# Smart_Coaster_rev1.net
KiCad netlist of a schematic drawn in EasyEDA Pro
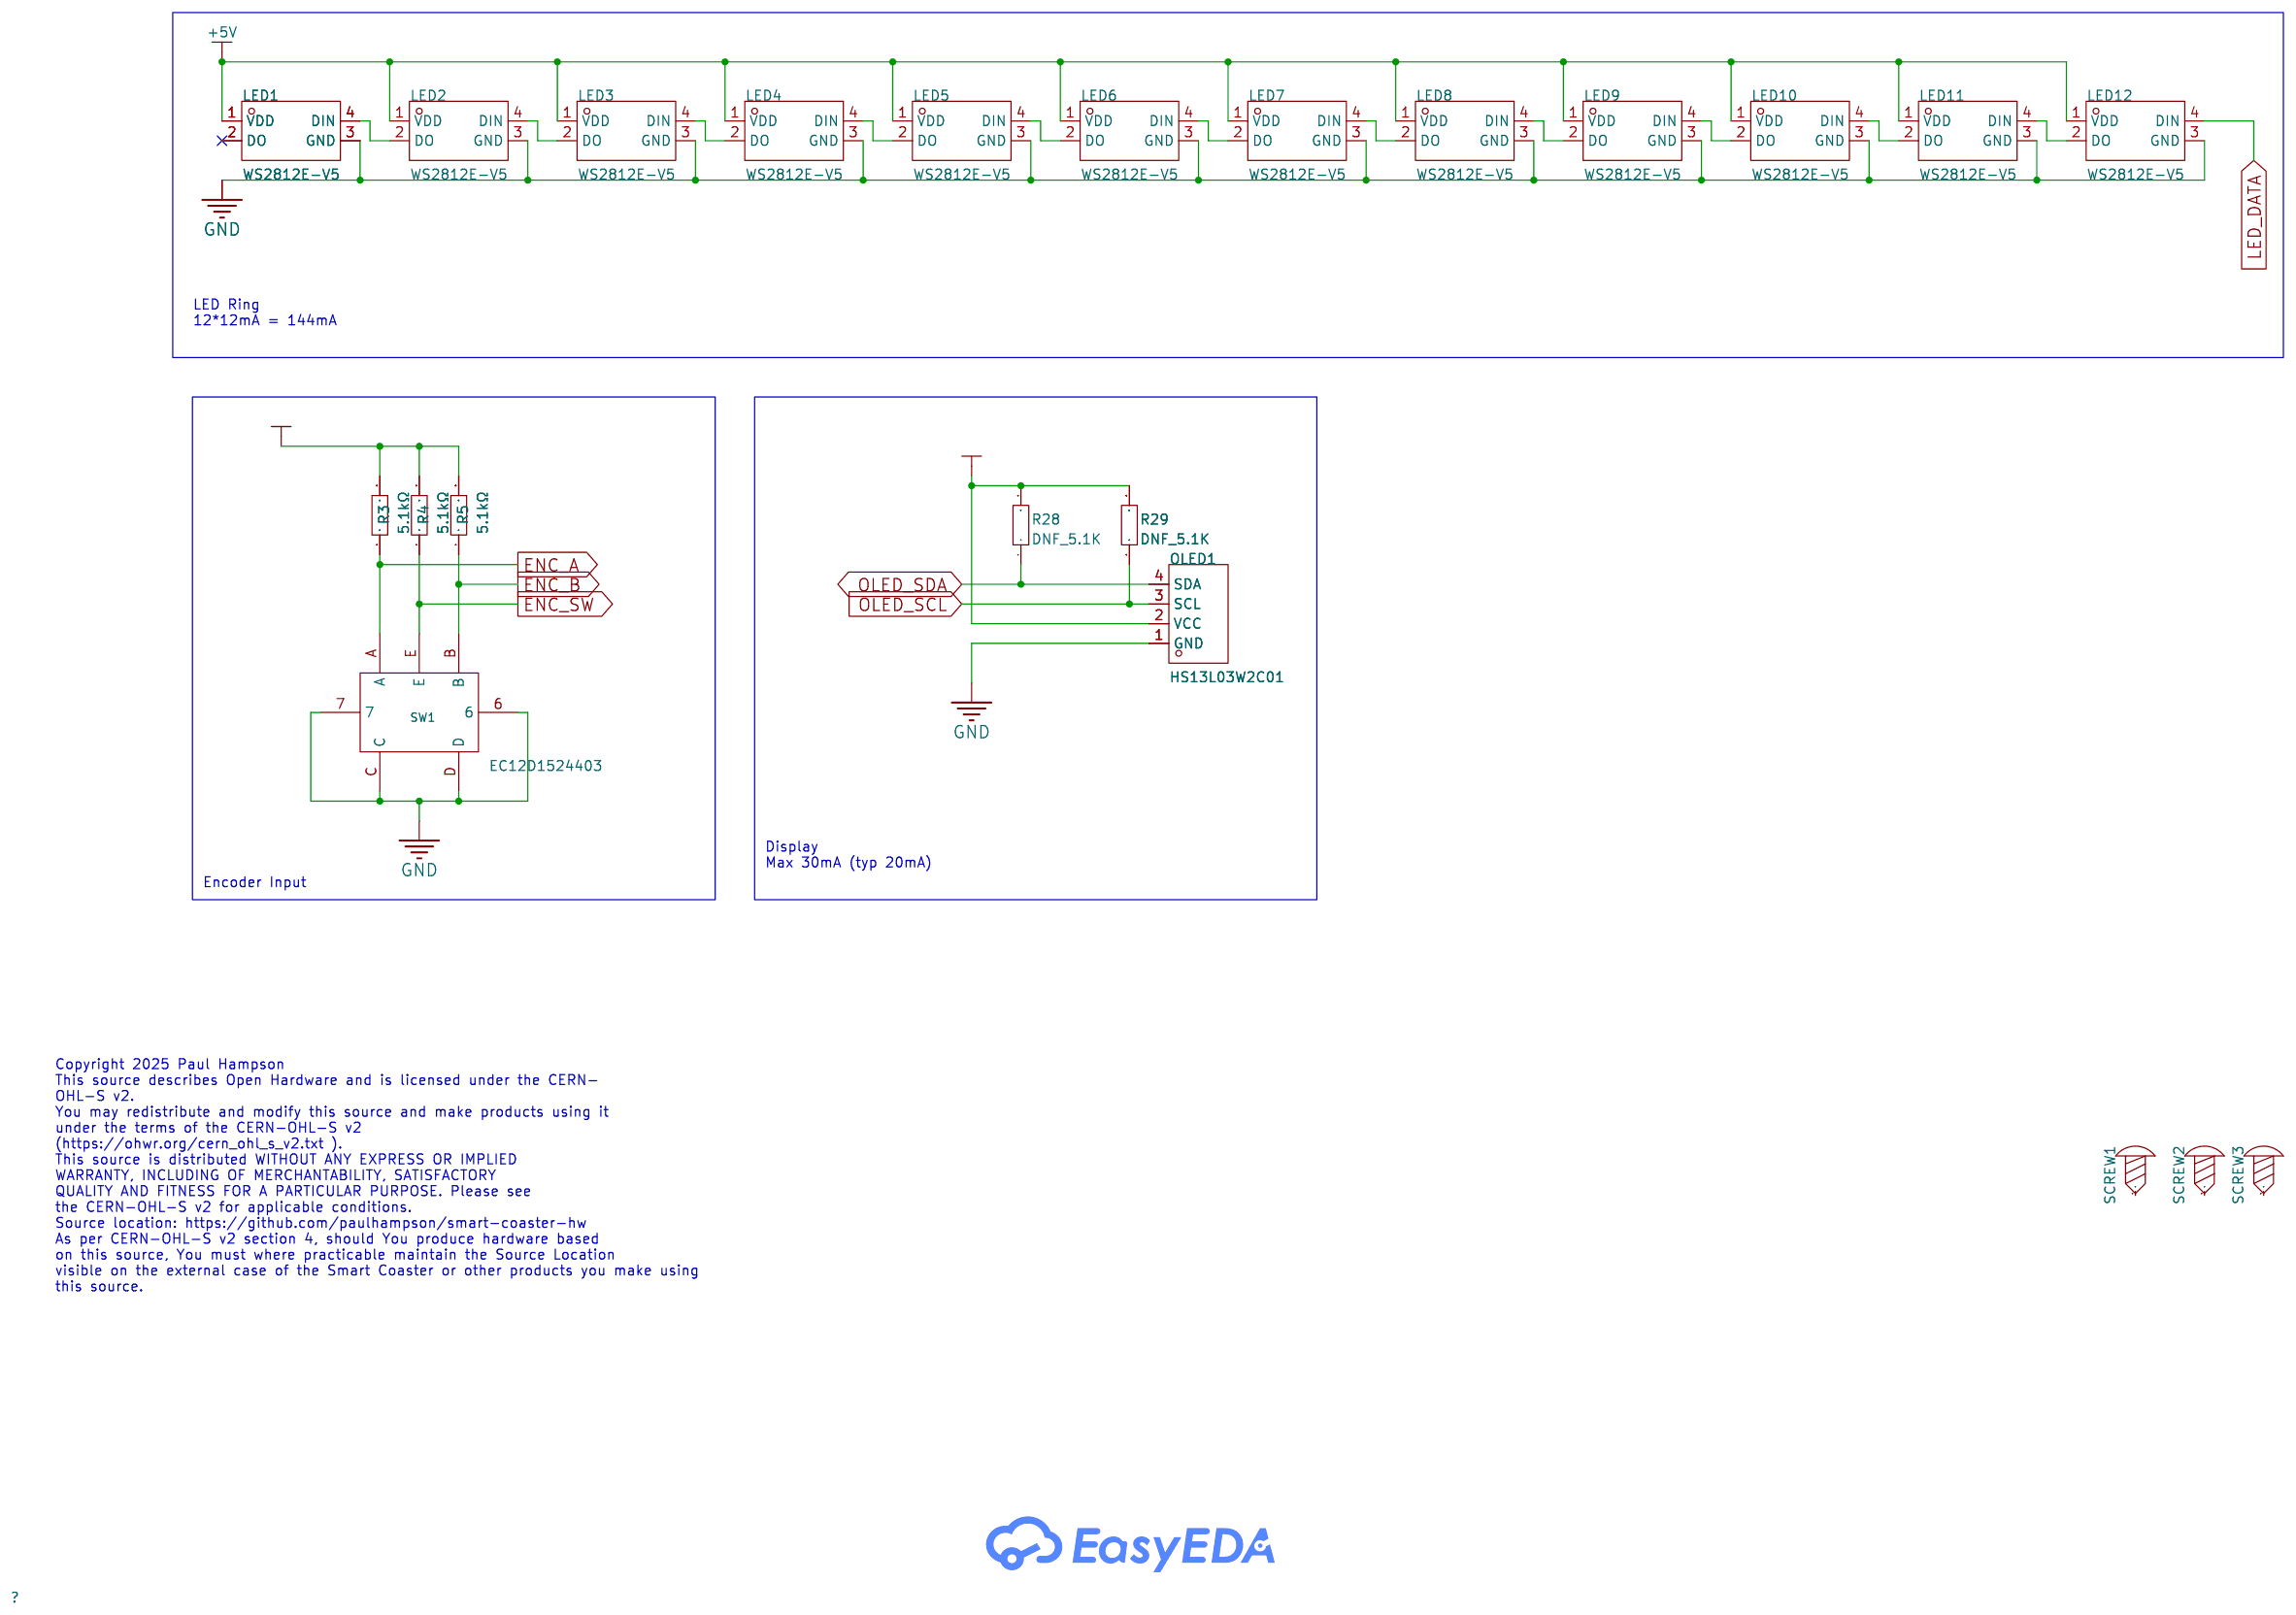
[diagram p0: HMI]
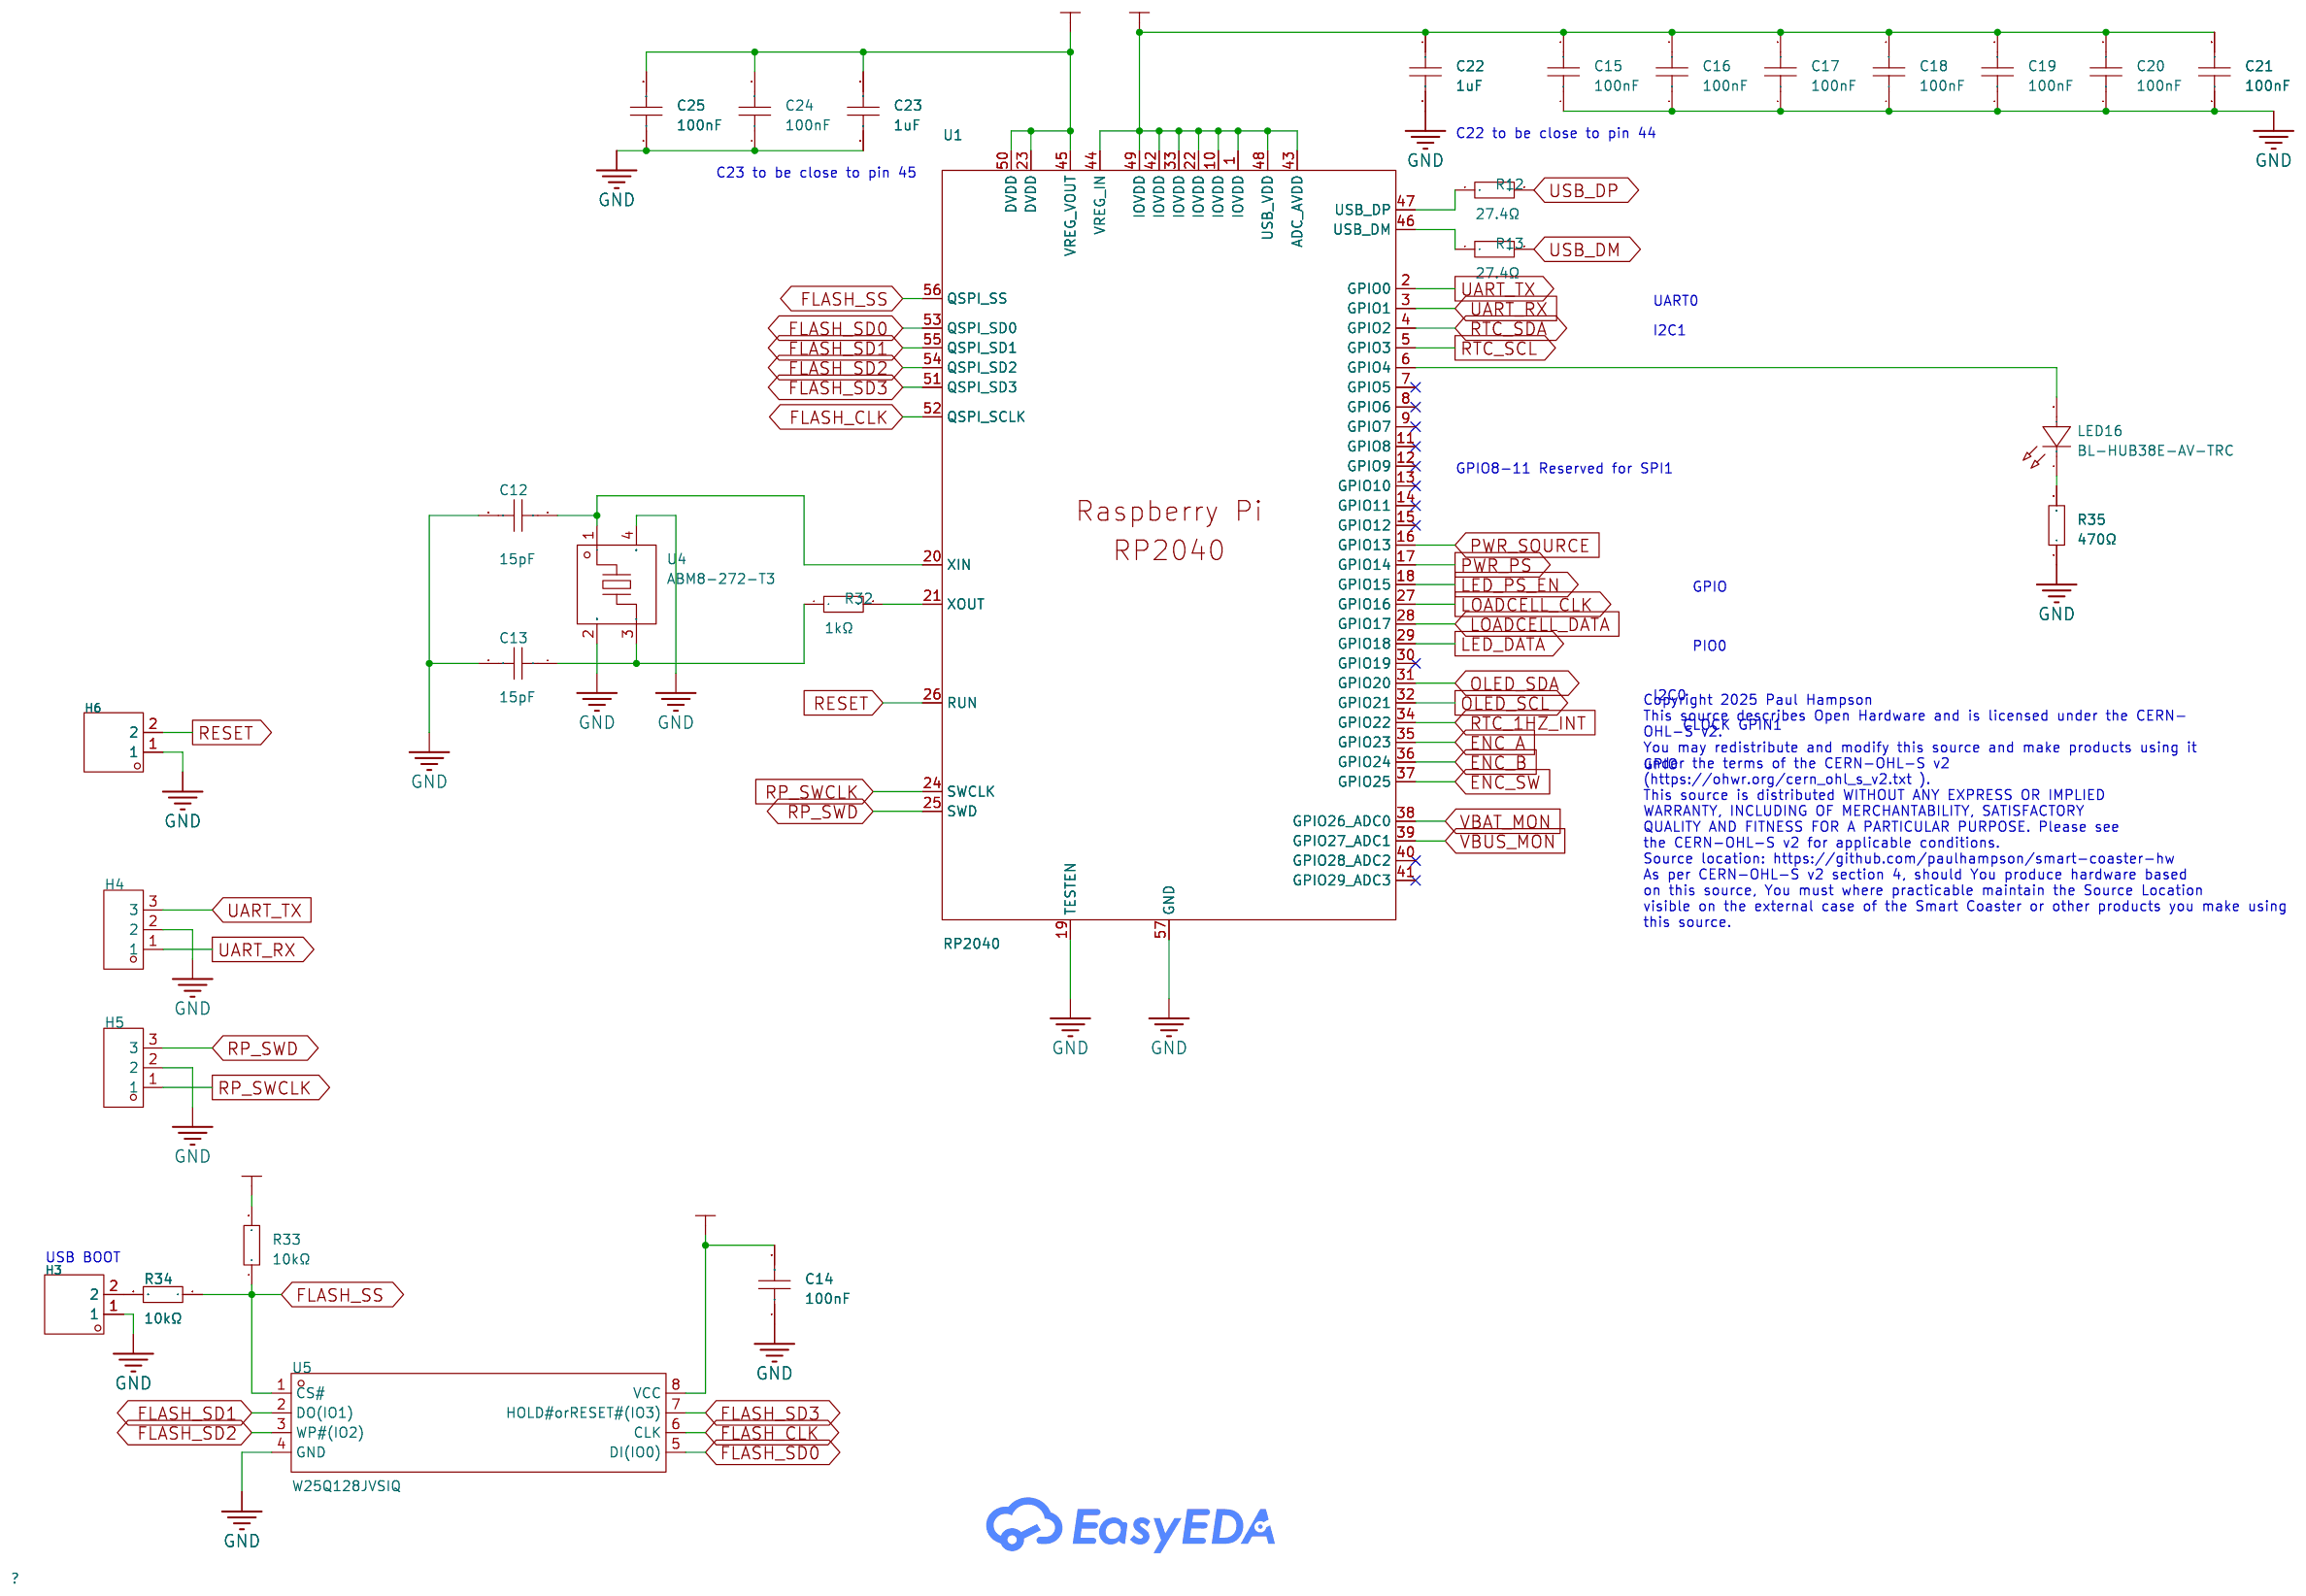
[diagram p1: Processor]
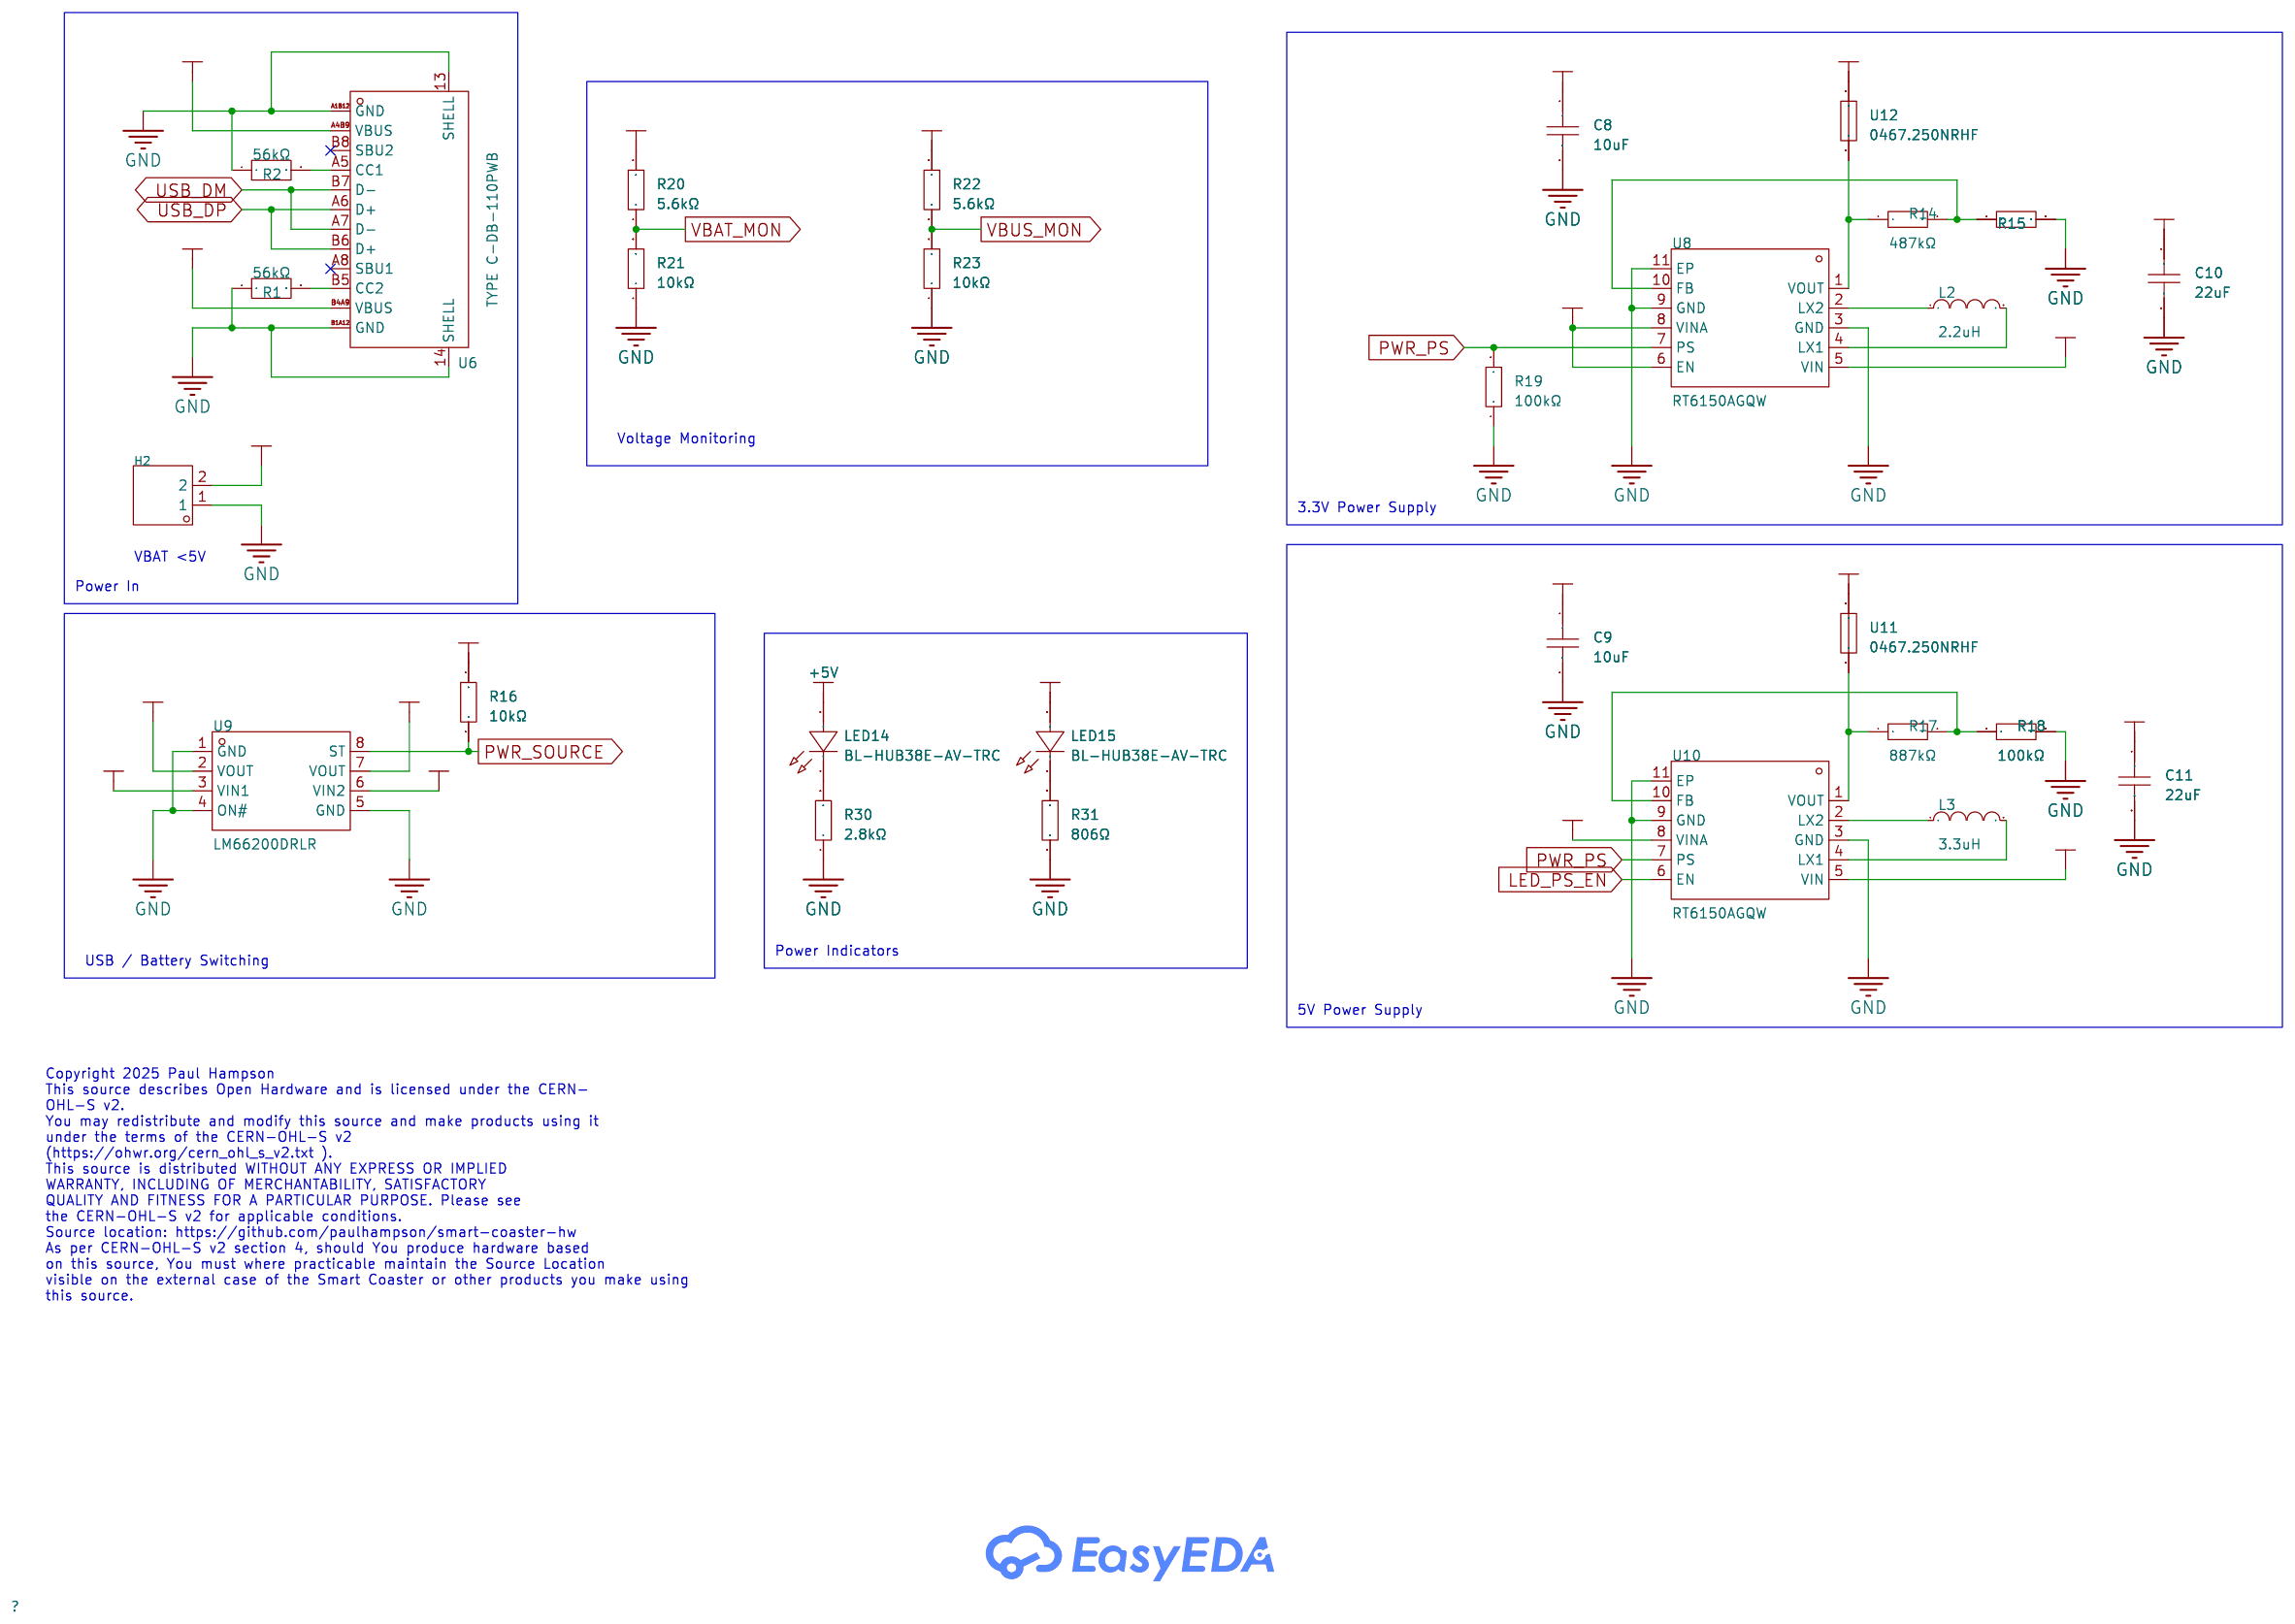
[diagram p2: Power]
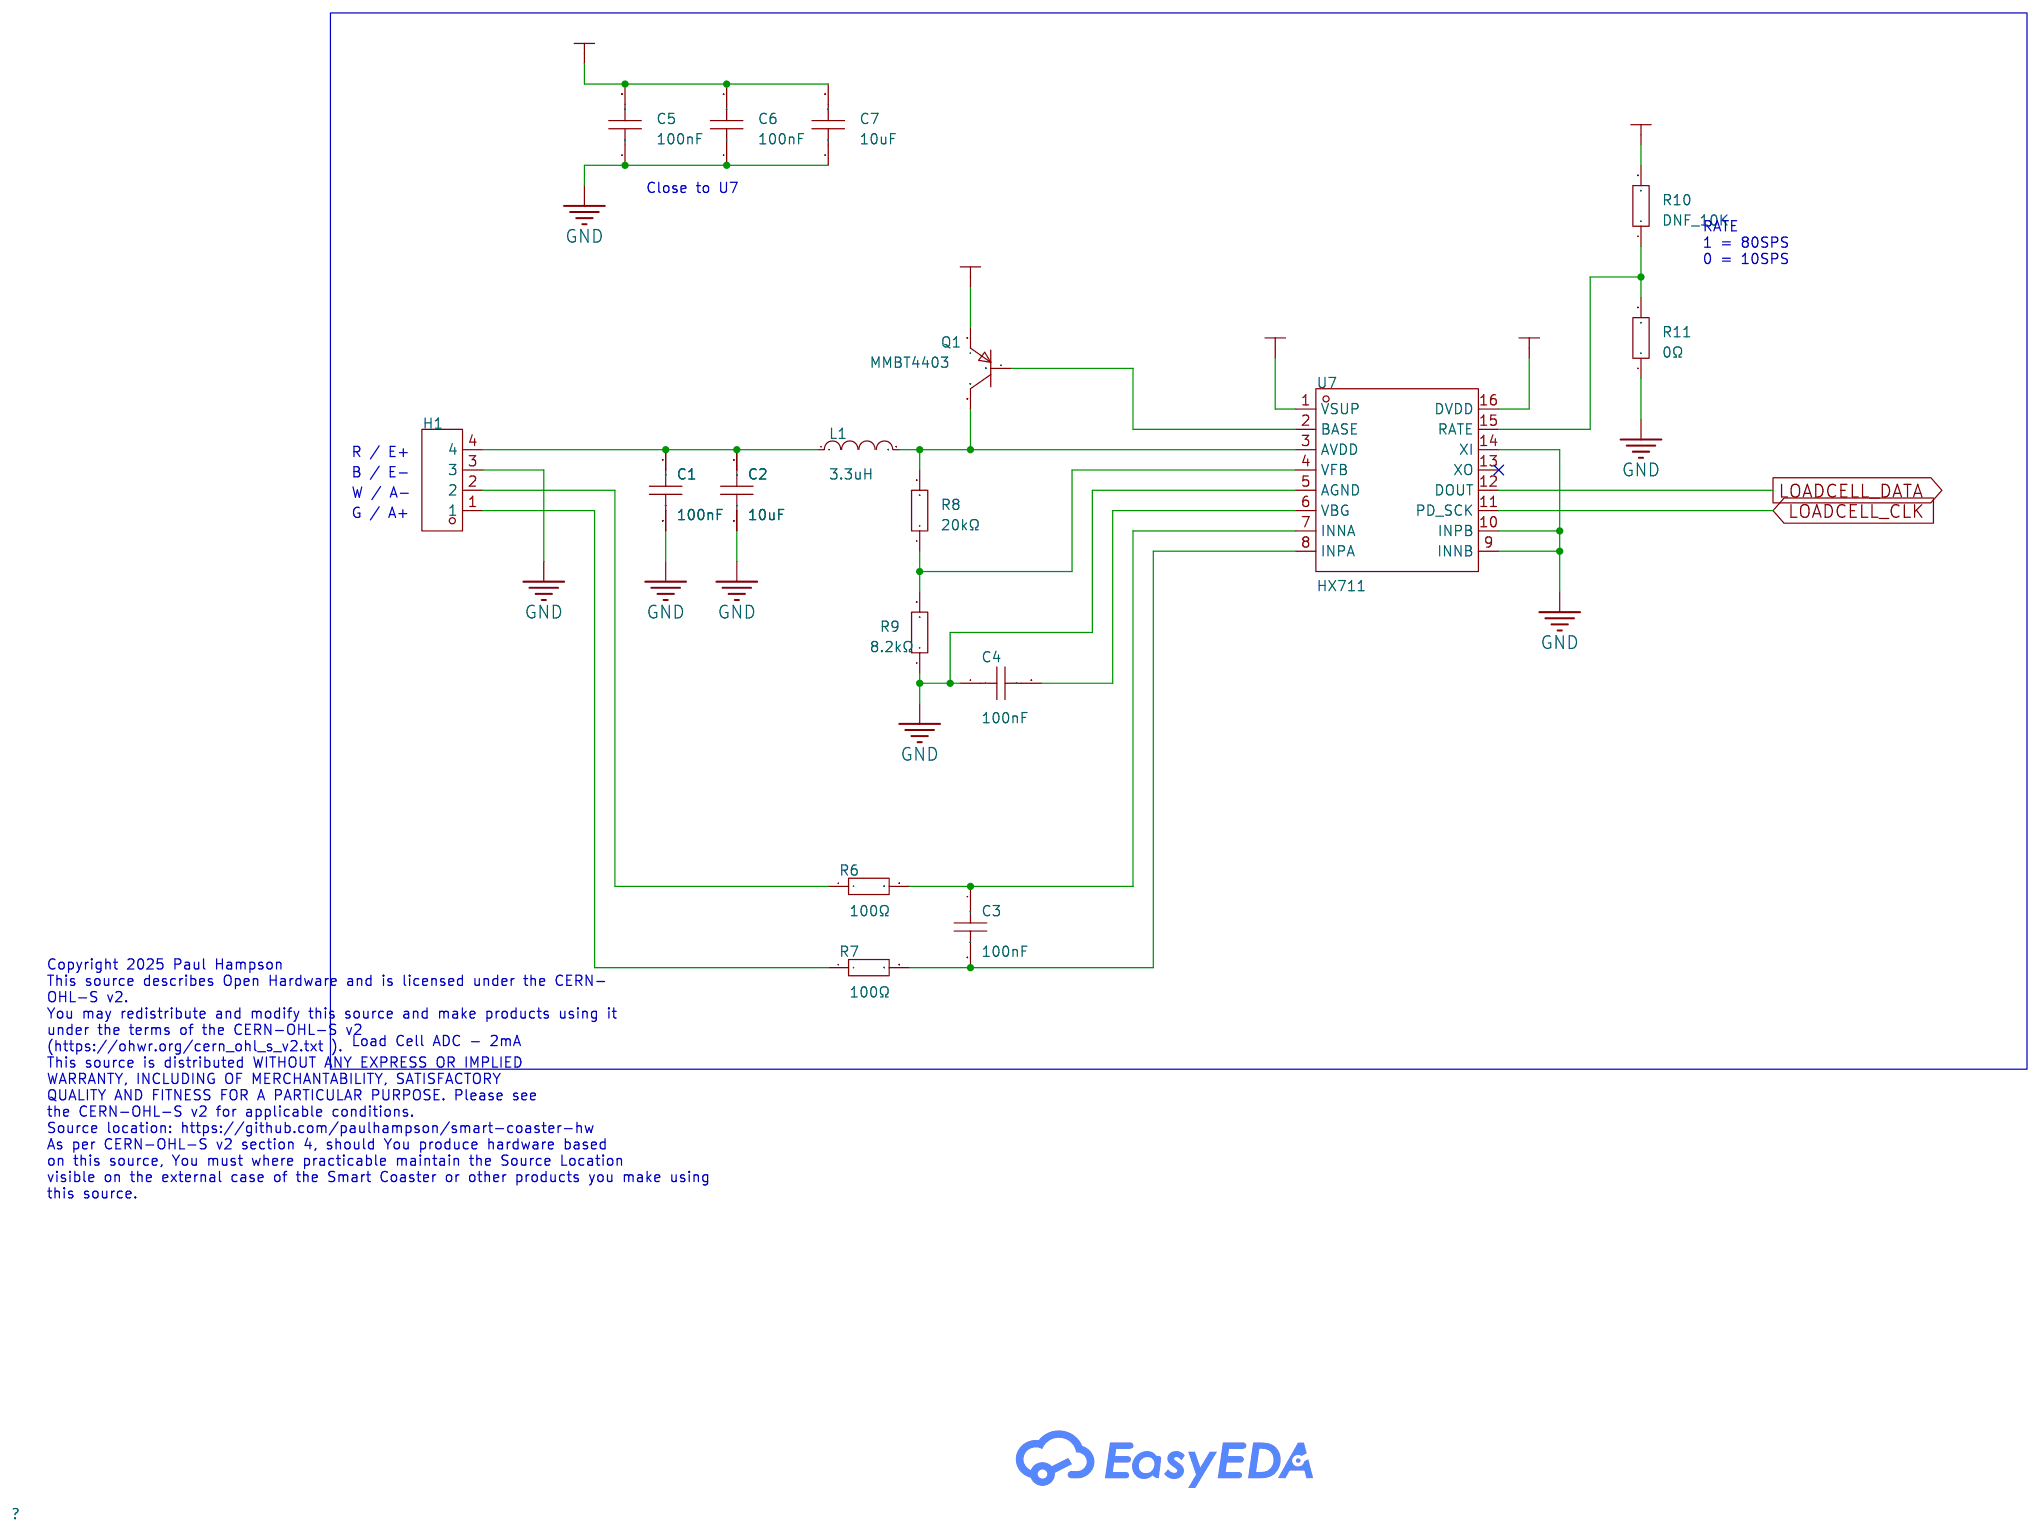
[diagram p3: Load Cell]
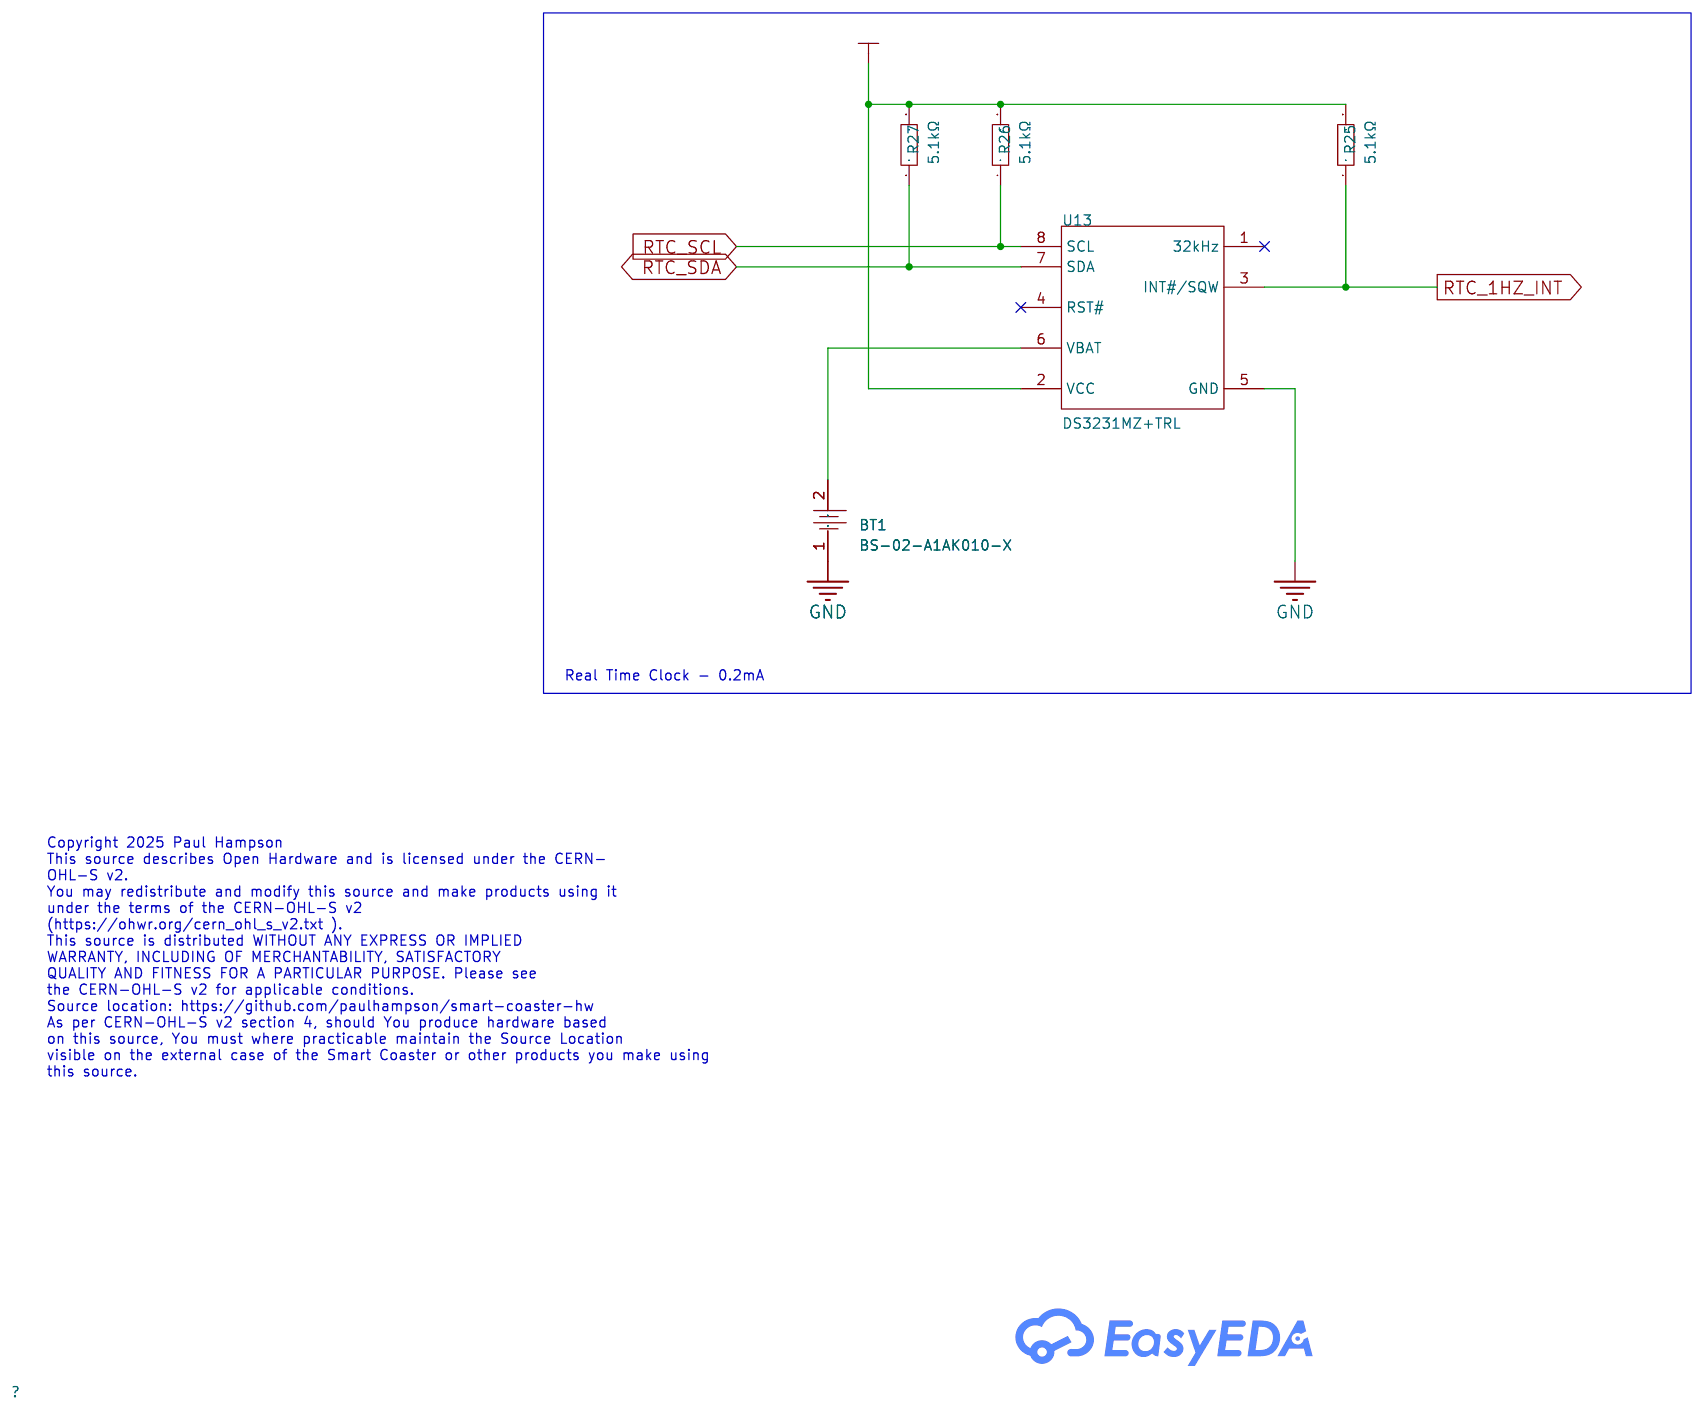
[diagram p4: RTC]

(export (version "E")
  (design (tool "Eeschema 10.0.6"))
  (components
    (comp (ref "LED1")
      (value "WS2812E-V5")
      (footprint "easyedapro:LED-SMD_4P-L5.0-W5.0-LS5.4-TL-1")
      (fields (field (name "Manufacturer") "worldsemi"))
      (libsource (lib "easyedapro") (part "WS2812E-V5"))
    )
    (comp (ref "LED2")
      (value "WS2812E-V5")
      (footprint "easyedapro:LED-SMD_4P-L5.0-W5.0-LS5.4-TL-1")
      (fields (field (name "Manufacturer") "worldsemi"))
      (libsource (lib "easyedapro") (part "WS2812E-V5"))
    )
    (comp (ref "LED3")
      (value "WS2812E-V5")
      (footprint "easyedapro:LED-SMD_4P-L5.0-W5.0-LS5.4-TL-1")
      (fields (field (name "Manufacturer") "worldsemi"))
      (libsource (lib "easyedapro") (part "WS2812E-V5"))
    )
    (comp (ref "LED4")
      (value "WS2812E-V5")
      (footprint "easyedapro:LED-SMD_4P-L5.0-W5.0-LS5.4-TL-1")
      (fields (field (name "Manufacturer") "worldsemi"))
      (libsource (lib "easyedapro") (part "WS2812E-V5"))
    )
    (comp (ref "LED5")
      (value "WS2812E-V5")
      (footprint "easyedapro:LED-SMD_4P-L5.0-W5.0-LS5.4-TL-1")
      (fields (field (name "Manufacturer") "worldsemi"))
      (libsource (lib "easyedapro") (part "WS2812E-V5"))
    )
    (comp (ref "LED6")
      (value "WS2812E-V5")
      (footprint "easyedapro:LED-SMD_4P-L5.0-W5.0-LS5.4-TL-1")
      (fields (field (name "Manufacturer") "worldsemi"))
      (libsource (lib "easyedapro") (part "WS2812E-V5"))
    )
    (comp (ref "LED7")
      (value "WS2812E-V5")
      (footprint "easyedapro:LED-SMD_4P-L5.0-W5.0-LS5.4-TL-1")
      (fields (field (name "Manufacturer") "worldsemi"))
      (libsource (lib "easyedapro") (part "WS2812E-V5"))
    )
    (comp (ref "LED8")
      (value "WS2812E-V5")
      (footprint "easyedapro:LED-SMD_4P-L5.0-W5.0-LS5.4-TL-1")
      (fields (field (name "Manufacturer") "worldsemi"))
      (libsource (lib "easyedapro") (part "WS2812E-V5"))
    )
    (comp (ref "LED9")
      (value "WS2812E-V5")
      (footprint "easyedapro:LED-SMD_4P-L5.0-W5.0-LS5.4-TL-1")
      (fields (field (name "Manufacturer") "worldsemi"))
      (libsource (lib "easyedapro") (part "WS2812E-V5"))
    )
    (comp (ref "LED10")
      (value "WS2812E-V5")
      (footprint "easyedapro:LED-SMD_4P-L5.0-W5.0-LS5.4-TL-1")
      (fields (field (name "Manufacturer") "worldsemi"))
      (libsource (lib "easyedapro") (part "WS2812E-V5"))
    )
    (comp (ref "LED11")
      (value "WS2812E-V5")
      (footprint "easyedapro:LED-SMD_4P-L5.0-W5.0-LS5.4-TL-1")
      (fields (field (name "Manufacturer") "worldsemi"))
      (libsource (lib "easyedapro") (part "WS2812E-V5"))
    )
    (comp (ref "LED12")
      (value "WS2812E-V5")
      (footprint "easyedapro:LED-SMD_4P-L5.0-W5.0-LS5.4-TL-1")
      (fields (field (name "Manufacturer") "worldsemi"))
      (libsource (lib "easyedapro") (part "WS2812E-V5"))
    )
    (comp (ref "OLED1")
      (value "HS13L03W2C01")
      (footprint "easyedapro:OLED-TH_L35.4-W33.5_HS13L03W2C01")
      (fields (field (name "Manufacturer") "HS(汉昇)"))
      (libsource (lib "easyedapro") (part "HS13L03W2C01"))
    )
    (comp (ref "R3")
      (value "5.1kΩ")
      (footprint "easyedapro:R0603")
      (fields
        (field (name "Manufacturer Part") "0603WAF5101T5E")
        (field (name "Manufacturer") "UNI-ROYAL(厚声)")
      )
      (libsource (lib "easyedapro") (part "0603WAF5101T5E"))
    )
    (comp (ref "R4")
      (value "5.1kΩ")
      (footprint "easyedapro:R0603")
      (fields
        (field (name "Manufacturer Part") "0603WAF5101T5E")
        (field (name "Manufacturer") "UNI-ROYAL(厚声)")
      )
      (libsource (lib "easyedapro") (part "0603WAF5101T5E"))
    )
    (comp (ref "R5")
      (value "5.1kΩ")
      (footprint "easyedapro:R0603")
      (fields
        (field (name "Manufacturer Part") "0603WAF5101T5E")
        (field (name "Manufacturer") "UNI-ROYAL(厚声)")
      )
      (libsource (lib "easyedapro") (part "0603WAF5101T5E"))
    )
    (comp (ref "R28")
      (value "DNF_5.1K")
      (footprint "easyedapro:R0402")
      (libsource (lib "easyedapro") (part "Res"))
    )
    (comp (ref "R29")
      (value "DNF_5.1K")
      (footprint "easyedapro:R0402")
      (libsource (lib "easyedapro") (part "Res"))
    )
    (comp (ref "SCREW1")
      (value "~")
      (footprint "easyedapro:Screw-Hole-M3")
      (libsource (lib "easyedapro") (part "Screw-Hole"))
    )
    (comp (ref "SCREW2")
      (value "~")
      (footprint "easyedapro:Screw-Hole-M3")
      (libsource (lib "easyedapro") (part "Screw-Hole"))
    )
    (comp (ref "SCREW3")
      (value "~")
      (footprint "easyedapro:Screw-Hole-M3")
      (libsource (lib "easyedapro") (part "Screw-Hole"))
    )
    (comp (ref "SW1")
      (value "EC12D1524403")
      (footprint "easyedapro:SW-TH_EC12D1524403")
      (fields (field (name "Manufacturer") "ALPSALPINE(阿尔卑斯阿尔派)"))
      (libsource (lib "easyedapro") (part "EC12D1524403"))
    )
    (comp (ref "C12")
      (value "15pF")
      (footprint "easyedapro:C0603")
      (fields
        (field (name "Manufacturer Part") "CC0402JRNPO9BN150")
        (field (name "Manufacturer") "YAGEO(国巨)")
      )
      (libsource (lib "easyedapro") (part "CAP"))
    )
    (comp (ref "C13")
      (value "15pF")
      (footprint "easyedapro:C0603")
      (fields
        (field (name "Manufacturer Part") "CC0402JRNPO9BN150")
        (field (name "Manufacturer") "YAGEO(国巨)")
      )
      (libsource (lib "easyedapro") (part "CAP"))
    )
    (comp (ref "C14")
      (value "100nF")
      (footprint "easyedapro:C0402")
      (fields
        (field (name "Manufacturer Part") "CL05B104KO5NNNC")
        (field (name "Manufacturer") "SAMSUNG(三星)")
      )
      (libsource (lib "easyedapro") (part "CL05B104KO5NNNC"))
    )
    (comp (ref "C15")
      (value "100nF")
      (footprint "easyedapro:C0402")
      (fields
        (field (name "Manufacturer Part") "CL05B104KO5NNNC")
        (field (name "Manufacturer") "SAMSUNG(三星)")
      )
      (libsource (lib "easyedapro") (part "CL05B104KO5NNNC"))
    )
    (comp (ref "C16")
      (value "100nF")
      (footprint "easyedapro:C0402")
      (fields
        (field (name "Manufacturer Part") "CL05B104KO5NNNC")
        (field (name "Manufacturer") "SAMSUNG(三星)")
      )
      (libsource (lib "easyedapro") (part "CL05B104KO5NNNC"))
    )
    (comp (ref "C17")
      (value "100nF")
      (footprint "easyedapro:C0402")
      (fields
        (field (name "Manufacturer Part") "CL05B104KO5NNNC")
        (field (name "Manufacturer") "SAMSUNG(三星)")
      )
      (libsource (lib "easyedapro") (part "CL05B104KO5NNNC"))
    )
    (comp (ref "C18")
      (value "100nF")
      (footprint "easyedapro:C0402")
      (fields
        (field (name "Manufacturer Part") "CL05B104KO5NNNC")
        (field (name "Manufacturer") "SAMSUNG(三星)")
      )
      (libsource (lib "easyedapro") (part "CL05B104KO5NNNC"))
    )
    (comp (ref "C19")
      (value "100nF")
      (footprint "easyedapro:C0402")
      (fields
        (field (name "Manufacturer Part") "CL05B104KO5NNNC")
        (field (name "Manufacturer") "SAMSUNG(三星)")
      )
      (libsource (lib "easyedapro") (part "CL05B104KO5NNNC"))
    )
    (comp (ref "C20")
      (value "100nF")
      (footprint "easyedapro:C0402")
      (fields
        (field (name "Manufacturer Part") "CL05B104KO5NNNC")
        (field (name "Manufacturer") "SAMSUNG(三星)")
      )
      (libsource (lib "easyedapro") (part "CL05B104KO5NNNC"))
    )
    (comp (ref "C21")
      (value "100nF")
      (footprint "easyedapro:C0402")
      (fields
        (field (name "Manufacturer Part") "CL05B104KO5NNNC")
        (field (name "Manufacturer") "SAMSUNG(三星)")
      )
      (libsource (lib "easyedapro") (part "CL05B104KO5NNNC"))
    )
    (comp (ref "C22")
      (value "1uF")
      (footprint "easyedapro:C0603")
      (fields
        (field (name "Manufacturer Part") "CL05A105KP5NNNC")
        (field (name "Manufacturer") "SAMSUNG(三星)")
      )
      (libsource (lib "easyedapro") (part "CAP"))
    )
    (comp (ref "C23")
      (value "1uF")
      (footprint "easyedapro:C0603")
      (fields
        (field (name "Manufacturer Part") "CL05A105KP5NNNC")
        (field (name "Manufacturer") "SAMSUNG(三星)")
      )
      (libsource (lib "easyedapro") (part "CAP"))
    )
    (comp (ref "C24")
      (value "100nF")
      (footprint "easyedapro:C0402")
      (fields
        (field (name "Manufacturer Part") "CL05B104KO5NNNC")
        (field (name "Manufacturer") "SAMSUNG(三星)")
      )
      (libsource (lib "easyedapro") (part "CL05B104KO5NNNC"))
    )
    (comp (ref "C25")
      (value "100nF")
      (footprint "easyedapro:C0402")
      (fields
        (field (name "Manufacturer Part") "CL05B104KO5NNNC")
        (field (name "Manufacturer") "SAMSUNG(三星)")
      )
      (libsource (lib "easyedapro") (part "CL05B104KO5NNNC"))
    )
    (comp (ref "H3")
      (value "~")
      (footprint "easyedapro:HDR-TH_2P-P2.54-V-M-1")
      (libsource (lib "easyedapro") (part "210S-1*2P L=11.6MMGold-plated black"))
    )
    (comp (ref "H4")
      (value "~")
      (footprint "easyedapro:HDR-TH_3P-P2.54-V-M")
      (libsource (lib "easyedapro") (part "PZ254V-11-03P_C2937625"))
    )
    (comp (ref "H5")
      (value "~")
      (footprint "easyedapro:HDR-TH_3P-P2.54-V-M")
      (libsource (lib "easyedapro") (part "PZ254V-11-03P_C2937625"))
    )
    (comp (ref "H6")
      (value "~")
      (footprint "easyedapro:HDR-TH_2P-P2.54-V-M-1")
      (libsource (lib "easyedapro") (part "210S-1*2P L=11.6MMGold-plated black"))
    )
    (comp (ref "LED16")
      (value "BL-HUB38E-AV-TRC")
      (footprint "easyedapro:LED-SMD_L1.7-W1.1-RD_RED-SIDE")
      (description "Emitted Color:Red Forward Current:-")
      (fields (field (name "Manufacturer") "BrtLed(佰鸿)"))
      (libsource (lib "easyedapro") (part "BL-HUB38E-AV-TRC"))
    )
    (comp (ref "R12")
      (value "27.4Ω")
      (footprint "easyedapro:R0402")
      (fields
        (field (name "Manufacturer Part") "0402WGF274JTCE")
        (field (name "Manufacturer") "UNI-ROYAL(厚声)")
      )
      (libsource (lib "easyedapro") (part "Res"))
    )
    (comp (ref "R13")
      (value "27.4Ω")
      (footprint "easyedapro:R0402")
      (fields
        (field (name "Manufacturer Part") "0402WGF274JTCE")
        (field (name "Manufacturer") "UNI-ROYAL(厚声)")
      )
      (libsource (lib "easyedapro") (part "Res"))
    )
    (comp (ref "R32")
      (value "1kΩ")
      (footprint "easyedapro:R0402")
      (fields
        (field (name "Manufacturer Part") "0402WGF1001TCE")
        (field (name "Manufacturer") "UNI-ROYAL(厚声)")
      )
      (libsource (lib "easyedapro") (part "Res"))
    )
    (comp (ref "R33")
      (value "10kΩ")
      (footprint "easyedapro:R0402")
      (fields
        (field (name "Manufacturer Part") "0402WGJ0103TCE")
        (field (name "Manufacturer") "UNI-ROYAL(厚声)")
      )
      (libsource (lib "easyedapro") (part "Res"))
    )
    (comp (ref "R34")
      (value "10kΩ")
      (footprint "easyedapro:R0402")
      (fields
        (field (name "Manufacturer Part") "0402WGJ0103TCE")
        (field (name "Manufacturer") "UNI-ROYAL(厚声)")
      )
      (libsource (lib "easyedapro") (part "Res"))
    )
    (comp (ref "R35")
      (value "470Ω")
      (footprint "easyedapro:R0402")
      (fields
        (field (name "Manufacturer Part") "0402WGF4700TCE")
        (field (name "Manufacturer") "UNI-ROYAL(厚声)")
      )
      (libsource (lib "easyedapro") (part "Res"))
    )
    (comp (ref "U1")
      (value "RP2040")
      (footprint "easyedapro:LQFN-56_L7.0-W7.0-P0.4-EP")
      (fields (field (name "Manufacturer") "Raspberry Pi(树莓派)"))
      (libsource (lib "easyedapro") (part "RP2040"))
    )
    (comp (ref "U4")
      (value "ABM8-272-T3")
      (footprint "easyedapro:CRYSTAL-SMD_4P-L3.2-W2.5-BL")
      (fields (field (name "Manufacturer") "ABRACON"))
      (libsource (lib "easyedapro") (part "ABM8-272-T3_C20625731"))
    )
    (comp (ref "U5")
      (value "W25Q128JVSIQ")
      (footprint "easyedapro:SOIC-8_L5.3-W5.3-P1.27-LS8.0-BL")
      (fields (field (name "Manufacturer") "WINBOND(华邦)"))
      (libsource (lib "easyedapro") (part "W25Q128JVSIQ"))
    )
    (comp (ref "C8")
      (value "10uF")
      (footprint "easyedapro:C0603")
      (fields
        (field (name "Manufacturer Part") "CL10A106MQ8NNNC")
        (field (name "Manufacturer") "SAMSUNG(三星)")
      )
      (libsource (lib "easyedapro") (part "CAP"))
    )
    (comp (ref "C9")
      (value "10uF")
      (footprint "easyedapro:C0603")
      (fields
        (field (name "Manufacturer Part") "CL10A106MQ8NNNC")
        (field (name "Manufacturer") "SAMSUNG(三星)")
      )
      (libsource (lib "easyedapro") (part "CAP"))
    )
    (comp (ref "C10")
      (value "22uF")
      (footprint "easyedapro:C0603")
      (fields
        (field (name "Manufacturer Part") "CL21A226MAYNNNE")
        (field (name "Manufacturer") "SAMSUNG(三星)")
      )
      (libsource (lib "easyedapro") (part "CAP"))
    )
    (comp (ref "C11")
      (value "22uF")
      (footprint "easyedapro:C0603")
      (fields
        (field (name "Manufacturer Part") "CL21A226MAYNNNE")
        (field (name "Manufacturer") "SAMSUNG(三星)")
      )
      (libsource (lib "easyedapro") (part "CAP"))
    )
    (comp (ref "H2")
      (value "~")
      (footprint "easyedapro:HDR-TH_2P-P2.54-V-M-1")
      (libsource (lib "easyedapro") (part "210S-1*2P L=11.6MMGold-plated black"))
    )
    (comp (ref "L2")
      (value "2.2uH")
      (footprint "easyedapro:L0603")
      (fields (field (name "Manufacturer Part") "AHW2012F-2R2KTF") (field (name "Manufacturer") "APV(爱普微)"))
      (libsource (lib "easyedapro") (part "电感"))
    )
    (comp (ref "L3")
      (value "3.3uH")
      (footprint "easyedapro:L0603")
      (fields (field (name "Manufacturer Part") "AHW2012F-3R3KTF") (field (name "Manufacturer") "APV(爱普微)"))
      (libsource (lib "easyedapro") (part "电感"))
    )
    (comp (ref "LED14")
      (value "BL-HUB38E-AV-TRC")
      (footprint "easyedapro:LED-SMD_L1.7-W1.1-RD_RED-SIDE")
      (description "Emitted Color:Red Forward Current:-")
      (fields (field (name "Manufacturer") "BrtLed(佰鸿)"))
      (libsource (lib "easyedapro") (part "BL-HUB38E-AV-TRC"))
    )
    (comp (ref "LED15")
      (value "BL-HUB38E-AV-TRC")
      (footprint "easyedapro:LED-SMD_L1.7-W1.1-RD_RED-SIDE")
      (description "Emitted Color:Red Forward Current:-")
      (fields (field (name "Manufacturer") "BrtLed(佰鸿)"))
      (libsource (lib "easyedapro") (part "BL-HUB38E-AV-TRC"))
    )
    (comp (ref "R1")
      (value "56kΩ")
      (footprint "easyedapro:R0603")
      (fields (field (name "Manufacturer Part") "SCR0603J56K") (field (name "Manufacturer") "VO(翔胜)"))
      (libsource (lib "easyedapro") (part "SCR0603J56K"))
    )
    (comp (ref "R2")
      (value "56kΩ")
      (footprint "easyedapro:R0603")
      (fields (field (name "Manufacturer Part") "SCR0603J56K") (field (name "Manufacturer") "VO(翔胜)"))
      (libsource (lib "easyedapro") (part "SCR0603J56K"))
    )
    (comp (ref "R14")
      (value "487kΩ")
      (footprint "easyedapro:R0402")
      (fields
        (field (name "Manufacturer Part") "0603WAF4873T5E")
        (field (name "Manufacturer") "UNI-ROYAL(厚声)")
      )
      (libsource (lib "easyedapro") (part "Res"))
    )
    (comp (ref "R15")
      (value "86.6kΩ")
      (footprint "easyedapro:R0603")
      (fields
        (field (name "Manufacturer Part") "0603WAF8662T5E")
        (field (name "Manufacturer") "UNI-ROYAL(厚声)")
      )
      (libsource (lib "easyedapro") (part "0603WAF8662T5E"))
    )
    (comp (ref "R16")
      (value "10kΩ")
      (footprint "easyedapro:R0402")
      (fields
        (field (name "Manufacturer Part") "0603WAF1002T5E")
        (field (name "Manufacturer") "UNI-ROYAL(厚声)")
      )
      (libsource (lib "easyedapro") (part "Res"))
    )
    (comp (ref "R17")
      (value "887kΩ")
      (footprint "easyedapro:R0402")
      (fields (field (name "Manufacturer Part") "ERJ3EKF8873V") (field (name "Manufacturer") "PANASONIC(松下)"))
      (libsource (lib "easyedapro") (part "Res"))
    )
    (comp (ref "R18")
      (value "100kΩ")
      (footprint "easyedapro:R0402")
      (fields
        (field (name "Manufacturer Part") "0603WAF1003T5E")
        (field (name "Manufacturer") "UNI-ROYAL(厚声)")
      )
      (libsource (lib "easyedapro") (part "Res"))
    )
    (comp (ref "R19")
      (value "100kΩ")
      (footprint "easyedapro:R0402")
      (fields
        (field (name "Manufacturer Part") "0603WAF1003T5E")
        (field (name "Manufacturer") "UNI-ROYAL(厚声)")
      )
      (libsource (lib "easyedapro") (part "Res"))
    )
    (comp (ref "R20")
      (value "5.6kΩ")
      (footprint "easyedapro:R0402")
      (fields
        (field (name "Manufacturer Part") "0805W8F5601T5E")
        (field (name "Manufacturer") "UNI-ROYAL(厚声)")
      )
      (libsource (lib "easyedapro") (part "Res"))
    )
    (comp (ref "R21")
      (value "10kΩ")
      (footprint "easyedapro:R0402")
      (fields
        (field (name "Manufacturer Part") "0603WAF1002T5E")
        (field (name "Manufacturer") "UNI-ROYAL(厚声)")
      )
      (libsource (lib "easyedapro") (part "Res"))
    )
    (comp (ref "R22")
      (value "5.6kΩ")
      (footprint "easyedapro:R0402")
      (fields
        (field (name "Manufacturer Part") "0805W8F5601T5E")
        (field (name "Manufacturer") "UNI-ROYAL(厚声)")
      )
      (libsource (lib "easyedapro") (part "Res"))
    )
    (comp (ref "R23")
      (value "10kΩ")
      (footprint "easyedapro:R0402")
      (fields
        (field (name "Manufacturer Part") "0603WAF1002T5E")
        (field (name "Manufacturer") "UNI-ROYAL(厚声)")
      )
      (libsource (lib "easyedapro") (part "Res"))
    )
    (comp (ref "R30")
      (value "2.8kΩ")
      (footprint "easyedapro:R0402")
      (fields
        (field (name "Manufacturer Part") "0402WGF2801TCE")
        (field (name "Manufacturer") "UNI-ROYAL(厚声)")
      )
      (libsource (lib "easyedapro") (part "Res"))
    )
    (comp (ref "R31")
      (value "806Ω")
      (footprint "easyedapro:R0402")
      (fields
        (field (name "Manufacturer Part") "0402WGF8060TCE")
        (field (name "Manufacturer") "UNI-ROYAL(厚声)")
      )
      (libsource (lib "easyedapro") (part "Res"))
    )
    (comp (ref "U6")
      (value "TYPE C-DB-110PWB")
      (footprint "easyedapro:USB-C-SMD_TYPE-C-DB-111PWB")
      (fields (field (name "Manufacturer") "HDGC(华德共创)"))
      (libsource (lib "easyedapro") (part "TYPE C-DB-110PWB"))
    )
    (comp (ref "U8")
      (value "RT6150AGQW")
      (footprint "easyedapro:WDFN-10_L3.0-W3.0-P0.50-BL-EP")
      (fields (field (name "Manufacturer") "RICHTEK(立锜)"))
      (libsource (lib "easyedapro") (part "RT6150AGQW"))
    )
    (comp (ref "U9")
      (value "LM66200DRLR")
      (footprint "easyedapro:SOT-583-8_L2.1-W1.2-P0.50-LS1.6-BL")
      (fields (field (name "Manufacturer") "TI(德州仪器)"))
      (libsource (lib "easyedapro") (part "LM66200DRLR"))
    )
    (comp (ref "U10")
      (value "RT6150AGQW")
      (footprint "easyedapro:WDFN-10_L3.0-W3.0-P0.50-BL-EP")
      (fields (field (name "Manufacturer") "RICHTEK(立锜)"))
      (libsource (lib "easyedapro") (part "RT6150AGQW"))
    )
    (comp (ref "U11")
      (value "0467.250NRHF")
      (footprint "easyedapro:F0603")
      (fields (field (name "Manufacturer") "Littelfuse(美国力特)"))
      (libsource (lib "easyedapro") (part "0467.250NRHF"))
    )
    (comp (ref "U12")
      (value "0467.250NRHF")
      (footprint "easyedapro:F0603")
      (fields (field (name "Manufacturer") "Littelfuse(美国力特)"))
      (libsource (lib "easyedapro") (part "0467.250NRHF"))
    )
    (comp (ref "C1")
      (value "100nF")
      (footprint "easyedapro:C0603")
      (fields
        (field (name "Manufacturer Part") "CGA0603X7R104K500JT")
        (field (name "Manufacturer") "HRE(芯声)")
      )
      (libsource (lib "easyedapro") (part "CAP"))
    )
    (comp (ref "C2")
      (value "10uF")
      (footprint "easyedapro:C0603")
      (fields
        (field (name "Manufacturer Part") "CL10A106MQ8NNNC")
        (field (name "Manufacturer") "SAMSUNG(三星)")
      )
      (libsource (lib "easyedapro") (part "CAP"))
    )
    (comp (ref "C3")
      (value "100nF")
      (footprint "easyedapro:C0603")
      (fields
        (field (name "Manufacturer Part") "CGA0603X7R104K500JT")
        (field (name "Manufacturer") "HRE(芯声)")
      )
      (libsource (lib "easyedapro") (part "CAP"))
    )
    (comp (ref "C4")
      (value "100nF")
      (footprint "easyedapro:C0603")
      (fields
        (field (name "Manufacturer Part") "CGA0603X7R104K500JT")
        (field (name "Manufacturer") "HRE(芯声)")
      )
      (libsource (lib "easyedapro") (part "CAP"))
    )
    (comp (ref "C5")
      (value "100nF")
      (footprint "easyedapro:C0603")
      (fields
        (field (name "Manufacturer Part") "CGA0603X7R104K500JT")
        (field (name "Manufacturer") "HRE(芯声)")
      )
      (libsource (lib "easyedapro") (part "CAP"))
    )
    (comp (ref "C6")
      (value "100nF")
      (footprint "easyedapro:C0603")
      (fields
        (field (name "Manufacturer Part") "CGA0603X7R104K500JT")
        (field (name "Manufacturer") "HRE(芯声)")
      )
      (libsource (lib "easyedapro") (part "CAP"))
    )
    (comp (ref "C7")
      (value "10uF")
      (footprint "easyedapro:C0603")
      (fields
        (field (name "Manufacturer Part") "CL10A106MQ8NNNC")
        (field (name "Manufacturer") "SAMSUNG(三星)")
      )
      (libsource (lib "easyedapro") (part "CAP"))
    )
    (comp (ref "H1")
      (value "~")
      (footprint "easyedapro:HDR-TH_4P-P2.54-V-M")
      (libsource (lib "easyedapro") (part "PZ254V-11-04P"))
    )
    (comp (ref "L1")
      (value "3.3uH")
      (footprint "easyedapro:L0603")
      (fields
        (field (name "Manufacturer Part") "SCL1608Q3R3KSP")
        (field (name "Manufacturer") "Sunltech(韩国顺磁)")
      )
      (libsource (lib "easyedapro") (part "电感"))
    )
    (comp (ref "Q1")
      (value "MMBT4403")
      (footprint "easyedapro:SOT-23-3_L2.9-W1.3-P1.90-LS2.4-BR")
      (fields (field (name "Manufacturer") "YANGJIE(扬杰)"))
      (libsource (lib "easyedapro") (part "MMBT4403_C699234"))
    )
    (comp (ref "R6")
      (value "100Ω")
      (footprint "easyedapro:R0402")
      (fields (field (name "Manufacturer Part") "RTT03101JTP") (field (name "Manufacturer") "RALEC(旺诠)"))
      (libsource (lib "easyedapro") (part "Res"))
    )
    (comp (ref "R7")
      (value "100Ω")
      (footprint "easyedapro:R0402")
      (fields (field (name "Manufacturer Part") "RTT03101JTP") (field (name "Manufacturer") "RALEC(旺诠)"))
      (libsource (lib "easyedapro") (part "Res"))
    )
    (comp (ref "R8")
      (value "20kΩ")
      (footprint "easyedapro:R0402")
      (fields
        (field (name "Manufacturer Part") "0603WAJ0203T5E")
        (field (name "Manufacturer") "UNI-ROYAL(厚声)")
      )
      (libsource (lib "easyedapro") (part "Res"))
    )
    (comp (ref "R9")
      (value "8.2kΩ")
      (footprint "easyedapro:R0402")
      (fields
        (field (name "Manufacturer Part") "0603WAJ0822T5E")
        (field (name "Manufacturer") "UNI-ROYAL(厚声)")
      )
      (libsource (lib "easyedapro") (part "Res"))
    )
    (comp (ref "R10")
      (value "DNF_10K")
      (footprint "easyedapro:R0402")
      (libsource (lib "easyedapro") (part "Res"))
    )
    (comp (ref "R11")
      (value "0Ω")
      (footprint "easyedapro:R0402")
      (fields (field (name "Manufacturer Part") "SCR0402J0R") (field (name "Manufacturer") "VO(翔胜)"))
      (libsource (lib "easyedapro") (part "Res"))
    )
    (comp (ref "U7")
      (value "HX711")
      (footprint "easyedapro:SOP-16_L10.0-W3.9-P1.27-LS6.0-BL")
      (fields (field (name "Manufacturer") "AVIA(海芯科技)"))
      (libsource (lib "easyedapro") (part "HX711_C6705483"))
    )
    (comp (ref "BT1")
      (value "BS-02-A1AK010-X")
      (footprint "easyedapro:BAT-TH_BS-02-A1AJ010")
      (fields (field (name "Manufacturer") "MYOUNG(美阳)"))
      (libsource (lib "easyedapro") (part "BS-02-A1AK010-X"))
    )
    (comp (ref "R25")
      (value "5.1kΩ")
      (footprint "easyedapro:R0603")
      (fields
        (field (name "Manufacturer Part") "0603WAF5101T5E")
        (field (name "Manufacturer") "UNI-ROYAL(厚声)")
      )
      (libsource (lib "easyedapro") (part "0603WAF5101T5E"))
    )
    (comp (ref "R26")
      (value "5.1kΩ")
      (footprint "easyedapro:R0603")
      (fields
        (field (name "Manufacturer Part") "0603WAF5101T5E")
        (field (name "Manufacturer") "UNI-ROYAL(厚声)")
      )
      (libsource (lib "easyedapro") (part "0603WAF5101T5E"))
    )
    (comp (ref "R27")
      (value "5.1kΩ")
      (footprint "easyedapro:R0603")
      (fields
        (field (name "Manufacturer Part") "0603WAF5101T5E")
        (field (name "Manufacturer") "UNI-ROYAL(厚声)")
      )
      (libsource (lib "easyedapro") (part "0603WAF5101T5E"))
    )
    (comp (ref "U13")
      (value "DS3231MZ+TRL")
      (footprint "easyedapro:SOIC-8_L4.9-W3.9-P1.27-LS6.0-BL")
      (fields (field (name "Manufacturer") "ADI(亚德诺)/MAXIM(美信)"))
      (libsource (lib "easyedapro") (part "DS3231MZ+"))
    )
  )
  (nets
    (net (code "1") (name "+5V") (class "Default")
      (node (ref "C11") (pin "1") (pinfunction "1_1") (pintype "input"))
      (node (ref "LED1") (pin "1") (pinfunction "VDD_1") (pintype "unspecified"))
      (node (ref "LED10") (pin "1") (pinfunction "VDD_1") (pintype "unspecified"))
      (node (ref "LED11") (pin "1") (pinfunction "VDD_1") (pintype "unspecified"))
      (node (ref "LED12") (pin "1") (pinfunction "VDD_1") (pintype "unspecified"))
      (node (ref "LED14") (pin "2") (pinfunction "A_2") (pintype "unspecified"))
      (node (ref "LED2") (pin "1") (pinfunction "VDD_1") (pintype "unspecified"))
      (node (ref "LED3") (pin "1") (pinfunction "VDD_1") (pintype "unspecified"))
      (node (ref "LED4") (pin "1") (pinfunction "VDD_1") (pintype "unspecified"))
      (node (ref "LED5") (pin "1") (pinfunction "VDD_1") (pintype "unspecified"))
      (node (ref "LED6") (pin "1") (pinfunction "VDD_1") (pintype "unspecified"))
      (node (ref "LED7") (pin "1") (pinfunction "VDD_1") (pintype "unspecified"))
      (node (ref "LED8") (pin "1") (pinfunction "VDD_1") (pintype "unspecified"))
      (node (ref "LED9") (pin "1") (pinfunction "VDD_1") (pintype "unspecified"))
      (node (ref "U11") (pin "2") (pinfunction "2_2") (pintype "input"))
    )
    (net (code "2") (name "1V1") (class "Default")
      (node (ref "C23") (pin "1") (pinfunction "1_1") (pintype "input"))
      (node (ref "C24") (pin "2") (pinfunction "2_2") (pintype "unspecified"))
      (node (ref "C25") (pin "2") (pinfunction "2_2") (pintype "unspecified"))
      (node (ref "U1") (pin "23") (pinfunction "DVDD_23") (pintype "bidirectional"))
      (node (ref "U1") (pin "45") (pinfunction "VREG_VOUT_45") (pintype "bidirectional"))
      (node (ref "U1") (pin "50") (pinfunction "DVDD_50") (pintype "bidirectional"))
    )
    (net (code "3") (name "3V3") (class "Default")
      (node (ref "C10") (pin "1") (pinfunction "1_1") (pintype "input"))
      (node (ref "C14") (pin "2") (pinfunction "2_2") (pintype "unspecified"))
      (node (ref "C15") (pin "2") (pinfunction "2_2") (pintype "unspecified"))
      (node (ref "C16") (pin "2") (pinfunction "2_2") (pintype "unspecified"))
      (node (ref "C17") (pin "2") (pinfunction "2_2") (pintype "unspecified"))
      (node (ref "C18") (pin "2") (pinfunction "2_2") (pintype "unspecified"))
      (node (ref "C19") (pin "2") (pinfunction "2_2") (pintype "unspecified"))
      (node (ref "C20") (pin "2") (pinfunction "2_2") (pintype "unspecified"))
      (node (ref "C21") (pin "2") (pinfunction "2_2") (pintype "unspecified"))
      (node (ref "C22") (pin "1") (pinfunction "1_1") (pintype "input"))
      (node (ref "C5") (pin "2") (pinfunction "2_2") (pintype "input"))
      (node (ref "C6") (pin "2") (pinfunction "2_2") (pintype "input"))
      (node (ref "C7") (pin "2") (pinfunction "2_2") (pintype "input"))
      (node (ref "LED15") (pin "2") (pinfunction "A_2") (pintype "unspecified"))
      (node (ref "OLED1") (pin "2") (pinfunction "VCC_2") (pintype "unspecified"))
      (node (ref "Q1") (pin "2") (pinfunction "E_2") (pintype "unspecified"))
      (node (ref "R10") (pin "2") (pinfunction "2_2") (pintype "input"))
      (node (ref "R25") (pin "2") (pinfunction "2_2") (pintype "input"))
      (node (ref "R26") (pin "2") (pinfunction "2_2") (pintype "input"))
      (node (ref "R27") (pin "2") (pinfunction "2_2") (pintype "input"))
      (node (ref "R28") (pin "2") (pinfunction "2_2") (pintype "input"))
      (node (ref "R29") (pin "2") (pinfunction "2_2") (pintype "input"))
      (node (ref "R3") (pin "2") (pinfunction "2_2") (pintype "input"))
      (node (ref "R33") (pin "2") (pinfunction "2_2") (pintype "input"))
      (node (ref "R4") (pin "2") (pinfunction "2_2") (pintype "input"))
      (node (ref "R5") (pin "2") (pinfunction "2_2") (pintype "input"))
      (node (ref "U1") (pin "1") (pinfunction "IOVDD_1") (pintype "bidirectional"))
      (node (ref "U1") (pin "10") (pinfunction "IOVDD_10") (pintype "bidirectional"))
      (node (ref "U1") (pin "22") (pinfunction "IOVDD_22") (pintype "bidirectional"))
      (node (ref "U1") (pin "33") (pinfunction "IOVDD_33") (pintype "bidirectional"))
      (node (ref "U1") (pin "42") (pinfunction "IOVDD_42") (pintype "bidirectional"))
      (node (ref "U1") (pin "43") (pinfunction "ADC_AVDD_43") (pintype "bidirectional"))
      (node (ref "U1") (pin "44") (pinfunction "VREG_IN_44") (pintype "bidirectional"))
      (node (ref "U1") (pin "48") (pinfunction "USB_VDD_48") (pintype "bidirectional"))
      (node (ref "U1") (pin "49") (pinfunction "IOVDD_49") (pintype "bidirectional"))
      (node (ref "U12") (pin "2") (pinfunction "2_2") (pintype "input"))
      (node (ref "U13") (pin "2") (pinfunction "VCC_2") (pintype "unspecified"))
      (node (ref "U5") (pin "8") (pinfunction "VCC_8") (pintype "input"))
      (node (ref "U7") (pin "1") (pinfunction "VSUP_1") (pintype "unspecified"))
      (node (ref "U7") (pin "16") (pinfunction "DVDD_16") (pintype "unspecified"))
    )
    (net (code "4") (name "ENC_A") (class "Default")
      (node (ref "R3") (pin "1") (pinfunction "1_1") (pintype "input"))
      (node (ref "SW1") (pin "A") (pinfunction "A_A") (pintype "input"))
      (node (ref "U1") (pin "35") (pinfunction "GPIO23_35") (pintype "bidirectional"))
    )
    (net (code "5") (name "ENC_B") (class "Default")
      (node (ref "R5") (pin "1") (pinfunction "1_1") (pintype "input"))
      (node (ref "SW1") (pin "B") (pinfunction "B_B") (pintype "input"))
      (node (ref "U1") (pin "36") (pinfunction "GPIO24_36") (pintype "bidirectional"))
    )
    (net (code "6") (name "ENC_SW") (class "Default")
      (node (ref "R4") (pin "1") (pinfunction "1_1") (pintype "input"))
      (node (ref "SW1") (pin "E") (pinfunction "E_E") (pintype "input"))
      (node (ref "U1") (pin "37") (pinfunction "GPIO25_37") (pintype "bidirectional"))
    )
    (net (code "7") (name "FLASH_CLK") (class "Default")
      (node (ref "U1") (pin "52") (pinfunction "QSPI_SCLK_52") (pintype "output"))
      (node (ref "U5") (pin "6") (pinfunction "CLK_6") (pintype "input"))
    )
    (net (code "8") (name "FLASH_SD0") (class "Default")
      (node (ref "U1") (pin "53") (pinfunction "QSPI_SD0_53") (pintype "bidirectional"))
      (node (ref "U5") (pin "5") (pinfunction "DI(IO0)_5") (pintype "input"))
    )
    (net (code "9") (name "FLASH_SD1") (class "Default")
      (node (ref "U1") (pin "55") (pinfunction "QSPI_SD1_55") (pintype "bidirectional"))
      (node (ref "U5") (pin "2") (pinfunction "DO(IO1)_2") (pintype "input"))
    )
    (net (code "10") (name "FLASH_SD2") (class "Default")
      (node (ref "U1") (pin "54") (pinfunction "QSPI_SD2_54") (pintype "bidirectional"))
      (node (ref "U5") (pin "3") (pinfunction "WP#(IO2)_3") (pintype "input"))
    )
    (net (code "11") (name "FLASH_SD3") (class "Default")
      (node (ref "U1") (pin "51") (pinfunction "QSPI_SD3_51") (pintype "bidirectional"))
      (node (ref "U5") (pin "7") (pinfunction "HOLD#orRESET#(IO3)_7") (pintype "input"))
    )
    (net (code "12") (name "FLASH_SS") (class "Default")
      (node (ref "R33") (pin "1") (pinfunction "1_1") (pintype "input"))
      (node (ref "R34") (pin "1") (pinfunction "1_1") (pintype "input"))
      (node (ref "U1") (pin "56") (pinfunction "QSPI_SS_56") (pintype "bidirectional"))
      (node (ref "U5") (pin "1") (pinfunction "CS#_1") (pintype "input"))
    )
    (net (code "13") (name "GND") (class "Default")
      (node (ref "BT1") (pin "1") (pinfunction "1_1") (pintype "input"))
      (node (ref "C1") (pin "2") (pinfunction "2_2") (pintype "input"))
      (node (ref "C10") (pin "2") (pinfunction "2_2") (pintype "input"))
      (node (ref "C11") (pin "2") (pinfunction "2_2") (pintype "input"))
      (node (ref "C12") (pin "2") (pinfunction "2_2") (pintype "input"))
      (node (ref "C13") (pin "2") (pinfunction "2_2") (pintype "input"))
      (node (ref "C14") (pin "1") (pinfunction "1_1") (pintype "unspecified"))
      (node (ref "C15") (pin "1") (pinfunction "1_1") (pintype "unspecified"))
      (node (ref "C16") (pin "1") (pinfunction "1_1") (pintype "unspecified"))
      (node (ref "C17") (pin "1") (pinfunction "1_1") (pintype "unspecified"))
      (node (ref "C18") (pin "1") (pinfunction "1_1") (pintype "unspecified"))
      (node (ref "C19") (pin "1") (pinfunction "1_1") (pintype "unspecified"))
      (node (ref "C2") (pin "2") (pinfunction "2_2") (pintype "input"))
      (node (ref "C20") (pin "1") (pinfunction "1_1") (pintype "unspecified"))
      (node (ref "C21") (pin "1") (pinfunction "1_1") (pintype "unspecified"))
      (node (ref "C22") (pin "2") (pinfunction "2_2") (pintype "input"))
      (node (ref "C23") (pin "2") (pinfunction "2_2") (pintype "input"))
      (node (ref "C24") (pin "1") (pinfunction "1_1") (pintype "unspecified"))
      (node (ref "C25") (pin "1") (pinfunction "1_1") (pintype "unspecified"))
      (node (ref "C4") (pin "1") (pinfunction "1_1") (pintype "input"))
      (node (ref "C5") (pin "1") (pinfunction "1_1") (pintype "input"))
      (node (ref "C6") (pin "1") (pinfunction "1_1") (pintype "input"))
      (node (ref "C7") (pin "1") (pinfunction "1_1") (pintype "input"))
      (node (ref "C8") (pin "2") (pinfunction "2_2") (pintype "input"))
      (node (ref "C9") (pin "2") (pinfunction "2_2") (pintype "input"))
      (node (ref "H1") (pin "3") (pinfunction "3_3") (pintype "unspecified"))
      (node (ref "H2") (pin "1") (pinfunction "1_1") (pintype "input"))
      (node (ref "H3") (pin "1") (pinfunction "1_1") (pintype "input"))
      (node (ref "H4") (pin "2") (pinfunction "2_2") (pintype "unspecified"))
      (node (ref "H5") (pin "2") (pinfunction "2_2") (pintype "unspecified"))
      (node (ref "H6") (pin "1") (pinfunction "1_1") (pintype "input"))
      (node (ref "LED1") (pin "3") (pinfunction "GND_3") (pintype "unspecified"))
      (node (ref "LED10") (pin "3") (pinfunction "GND_3") (pintype "unspecified"))
      (node (ref "LED11") (pin "3") (pinfunction "GND_3") (pintype "unspecified"))
      (node (ref "LED12") (pin "3") (pinfunction "GND_3") (pintype "unspecified"))
      (node (ref "LED2") (pin "3") (pinfunction "GND_3") (pintype "unspecified"))
      (node (ref "LED3") (pin "3") (pinfunction "GND_3") (pintype "unspecified"))
      (node (ref "LED4") (pin "3") (pinfunction "GND_3") (pintype "unspecified"))
      (node (ref "LED5") (pin "3") (pinfunction "GND_3") (pintype "unspecified"))
      (node (ref "LED6") (pin "3") (pinfunction "GND_3") (pintype "unspecified"))
      (node (ref "LED7") (pin "3") (pinfunction "GND_3") (pintype "unspecified"))
      (node (ref "LED8") (pin "3") (pinfunction "GND_3") (pintype "unspecified"))
      (node (ref "LED9") (pin "3") (pinfunction "GND_3") (pintype "unspecified"))
      (node (ref "OLED1") (pin "1") (pinfunction "GND_1") (pintype "unspecified"))
      (node (ref "R1") (pin "1") (pinfunction "1_1") (pintype "unspecified"))
      (node (ref "R11") (pin "1") (pinfunction "1_1") (pintype "input"))
      (node (ref "R15") (pin "2") (pinfunction "2_2") (pintype "input"))
      (node (ref "R18") (pin "2") (pinfunction "2_2") (pintype "input"))
      (node (ref "R19") (pin "1") (pinfunction "1_1") (pintype "input"))
      (node (ref "R2") (pin "1") (pinfunction "1_1") (pintype "unspecified"))
      (node (ref "R21") (pin "1") (pinfunction "1_1") (pintype "input"))
      (node (ref "R23") (pin "1") (pinfunction "1_1") (pintype "input"))
      (node (ref "R30") (pin "1") (pinfunction "1_1") (pintype "input"))
      (node (ref "R31") (pin "1") (pinfunction "1_1") (pintype "input"))
      (node (ref "R35") (pin "1") (pinfunction "1_1") (pintype "input"))
      (node (ref "R9") (pin "1") (pinfunction "1_1") (pintype "input"))
      (node (ref "SW1") (pin "6") (pinfunction "6_6") (pintype "input"))
      (node (ref "SW1") (pin "7") (pinfunction "7_7") (pintype "input"))
      (node (ref "SW1") (pin "C") (pinfunction "C_C") (pintype "input"))
      (node (ref "SW1") (pin "D") (pinfunction "D_D") (pintype "input"))
      (node (ref "U1") (pin "19") (pinfunction "TESTEN_19") (pintype "unspecified"))
      (node (ref "U1") (pin "57") (pinfunction "GND_57") (pintype "bidirectional"))
      (node (ref "U10") (pin "11") (pinfunction "EP_11") (pintype "unspecified"))
      (node (ref "U10") (pin "3") (pinfunction "GND_3") (pintype "unspecified"))
      (node (ref "U10") (pin "9") (pinfunction "GND_9") (pintype "unspecified"))
      (node (ref "U13") (pin "5") (pinfunction "GND_5") (pintype "unspecified"))
      (node (ref "U4") (pin "2") (pinfunction "GND_2") (pintype "input"))
      (node (ref "U4") (pin "4") (pinfunction "GND_4") (pintype "input"))
      (node (ref "U5") (pin "4") (pinfunction "GND_4") (pintype "input"))
      (node (ref "U6") (pin "13") (pinfunction "SHELL_13") (pintype "unspecified"))
      (node (ref "U6") (pin "14") (pinfunction "SHELL_14") (pintype "unspecified"))
      (node (ref "U6") (pin "A1B12") (pinfunction "GND_A1B12") (pintype "unspecified"))
      (node (ref "U6") (pin "B1A12") (pinfunction "GND_B1A12") (pintype "unspecified"))
      (node (ref "U7") (pin "10") (pinfunction "INPB_10") (pintype "unspecified"))
      (node (ref "U7") (pin "14") (pinfunction "XI_14") (pintype "unspecified"))
      (node (ref "U7") (pin "5") (pinfunction "AGND_5") (pintype "unspecified"))
      (node (ref "U7") (pin "9") (pinfunction "INNB_9") (pintype "unspecified"))
      (node (ref "U8") (pin "11") (pinfunction "EP_11") (pintype "unspecified"))
      (node (ref "U8") (pin "3") (pinfunction "GND_3") (pintype "unspecified"))
      (node (ref "U8") (pin "9") (pinfunction "GND_9") (pintype "unspecified"))
      (node (ref "U9") (pin "1") (pinfunction "GND_1") (pintype "unspecified"))
      (node (ref "U9") (pin "4") (pinfunction "ON#_4") (pintype "unspecified"))
      (node (ref "U9") (pin "5") (pinfunction "GND_5") (pintype "unspecified"))
    )
    (net (code "14") (name "LED_DATA") (class "Default")
      (node (ref "LED12") (pin "4") (pinfunction "DIN_4") (pintype "unspecified"))
      (node (ref "U1") (pin "29") (pinfunction "GPIO18_29") (pintype "bidirectional"))
    )
    (net (code "15") (name "LED_PS_EN") (class "Default")
      (node (ref "U1") (pin "18") (pinfunction "GPIO15_18") (pintype "bidirectional"))
      (node (ref "U10") (pin "6") (pinfunction "EN_6") (pintype "unspecified"))
    )
    (net (code "16") (name "LOADCELL_CLK") (class "Default")
      (node (ref "U1") (pin "27") (pinfunction "GPIO16_27") (pintype "bidirectional"))
      (node (ref "U7") (pin "11") (pinfunction "PD_SCK_11") (pintype "unspecified"))
    )
    (net (code "17") (name "LOADCELL_DATA") (class "Default")
      (node (ref "U1") (pin "28") (pinfunction "GPIO17_28") (pintype "bidirectional"))
      (node (ref "U7") (pin "12") (pinfunction "DOUT_12") (pintype "unspecified"))
    )
    (net (code "18") (name "Net-(C1-Pad1)") (class "Default")
      (node (ref "C1") (pin "1") (pinfunction "1_1") (pintype "input"))
      (node (ref "C2") (pin "1") (pinfunction "1_1") (pintype "input"))
      (node (ref "H1") (pin "4") (pinfunction "4_4") (pintype "unspecified"))
      (node (ref "L1") (pin "1") (pinfunction "1_1") (pintype "input"))
    )
    (net (code "19") (name "Net-(C13-Pad1)") (class "Default")
      (node (ref "C13") (pin "1") (pinfunction "1_1") (pintype "input"))
      (node (ref "R32") (pin "1") (pinfunction "1_1") (pintype "input"))
      (node (ref "U4") (pin "3") (pinfunction "3_3") (pintype "input"))
    )
    (net (code "20") (name "Net-(H1-Pad1)") (class "Default")
      (node (ref "H1") (pin "1") (pinfunction "1_1") (pintype "unspecified"))
      (node (ref "R7") (pin "1") (pinfunction "1_1") (pintype "input"))
    )
    (net (code "21") (name "Net-(H1-Pad2)") (class "Default")
      (node (ref "H1") (pin "2") (pinfunction "2_2") (pintype "unspecified"))
      (node (ref "R6") (pin "1") (pinfunction "1_1") (pintype "input"))
    )
    (net (code "22") (name "Net-(H3-Pad2)") (class "Default")
      (node (ref "H3") (pin "2") (pinfunction "2_2") (pintype "input"))
      (node (ref "R34") (pin "2") (pinfunction "2_2") (pintype "input"))
    )
    (net (code "23") (name "Net-(LED1-DIN)") (class "Default")
      (node (ref "LED1") (pin "4") (pinfunction "DIN_4") (pintype "unspecified"))
      (node (ref "LED2") (pin "2") (pinfunction "DO_2") (pintype "unspecified"))
    )
    (net (code "24") (name "Net-(LED2-DIN)") (class "Default")
      (node (ref "LED2") (pin "4") (pinfunction "DIN_4") (pintype "unspecified"))
      (node (ref "LED3") (pin "2") (pinfunction "DO_2") (pintype "unspecified"))
    )
    (net (code "25") (name "Net-(LED3-DIN)") (class "Default")
      (node (ref "LED3") (pin "4") (pinfunction "DIN_4") (pintype "unspecified"))
      (node (ref "LED4") (pin "2") (pinfunction "DO_2") (pintype "unspecified"))
    )
    (net (code "26") (name "Net-(LED4-DIN)") (class "Default")
      (node (ref "LED4") (pin "4") (pinfunction "DIN_4") (pintype "unspecified"))
      (node (ref "LED5") (pin "2") (pinfunction "DO_2") (pintype "unspecified"))
    )
    (net (code "27") (name "Net-(LED5-DIN)") (class "Default")
      (node (ref "LED5") (pin "4") (pinfunction "DIN_4") (pintype "unspecified"))
      (node (ref "LED6") (pin "2") (pinfunction "DO_2") (pintype "unspecified"))
    )
    (net (code "28") (name "Net-(LED6-DIN)") (class "Default")
      (node (ref "LED6") (pin "4") (pinfunction "DIN_4") (pintype "unspecified"))
      (node (ref "LED7") (pin "2") (pinfunction "DO_2") (pintype "unspecified"))
    )
    (net (code "29") (name "Net-(LED7-DIN)") (class "Default")
      (node (ref "LED7") (pin "4") (pinfunction "DIN_4") (pintype "unspecified"))
      (node (ref "LED8") (pin "2") (pinfunction "DO_2") (pintype "unspecified"))
    )
    (net (code "30") (name "Net-(LED8-DIN)") (class "Default")
      (node (ref "LED8") (pin "4") (pinfunction "DIN_4") (pintype "unspecified"))
      (node (ref "LED9") (pin "2") (pinfunction "DO_2") (pintype "unspecified"))
    )
    (net (code "31") (name "Net-(LED10-DIN)") (class "Default")
      (node (ref "LED10") (pin "4") (pinfunction "DIN_4") (pintype "unspecified"))
      (node (ref "LED11") (pin "2") (pinfunction "DO_2") (pintype "unspecified"))
    )
    (net (code "32") (name "Net-(LED10-DO)") (class "Default")
      (node (ref "LED10") (pin "2") (pinfunction "DO_2") (pintype "unspecified"))
      (node (ref "LED9") (pin "4") (pinfunction "DIN_4") (pintype "unspecified"))
    )
    (net (code "33") (name "Net-(LED11-DIN)") (class "Default")
      (node (ref "LED11") (pin "4") (pinfunction "DIN_4") (pintype "unspecified"))
      (node (ref "LED12") (pin "2") (pinfunction "DO_2") (pintype "unspecified"))
    )
    (net (code "34") (name "Net-(LED14-K)") (class "Default")
      (node (ref "LED14") (pin "1") (pinfunction "K_1") (pintype "unspecified"))
      (node (ref "R30") (pin "2") (pinfunction "2_2") (pintype "input"))
    )
    (net (code "35") (name "Net-(LED15-K)") (class "Default")
      (node (ref "LED15") (pin "1") (pinfunction "K_1") (pintype "unspecified"))
      (node (ref "R31") (pin "2") (pinfunction "2_2") (pintype "input"))
    )
    (net (code "36") (name "Net-(LED16-A)") (class "Default")
      (node (ref "LED16") (pin "2") (pinfunction "A_2") (pintype "unspecified"))
      (node (ref "U1") (pin "6") (pinfunction "GPIO4_6") (pintype "bidirectional"))
    )
    (net (code "37") (name "Net-(LED16-K)") (class "Default")
      (node (ref "LED16") (pin "1") (pinfunction "K_1") (pintype "unspecified"))
      (node (ref "R35") (pin "2") (pinfunction "2_2") (pintype "input"))
    )
    (net (code "38") (name "Net-(Q1-B)") (class "Default")
      (node (ref "Q1") (pin "1") (pinfunction "B_1") (pintype "unspecified"))
      (node (ref "U7") (pin "2") (pinfunction "BASE_2") (pintype "unspecified"))
    )
    (net (code "39") (name "Net-(Q1-C)") (class "Default")
      (node (ref "L1") (pin "2") (pinfunction "2_2") (pintype "input"))
      (node (ref "Q1") (pin "3") (pinfunction "C_3") (pintype "unspecified"))
      (node (ref "R8") (pin "2") (pinfunction "2_2") (pintype "input"))
      (node (ref "U7") (pin "3") (pinfunction "AVDD_3") (pintype "unspecified"))
    )
    (net (code "40") (name "Net-(U1-USB_DM)") (class "Default")
      (node (ref "R13") (pin "1") (pinfunction "1_1") (pintype "input"))
      (node (ref "U1") (pin "46") (pinfunction "USB_DM_46") (pintype "bidirectional"))
    )
    (net (code "41") (name "Net-(U1-USB_DP)") (class "Default")
      (node (ref "R12") (pin "1") (pinfunction "1_1") (pintype "input"))
      (node (ref "U1") (pin "47") (pinfunction "USB_DP_47") (pintype "bidirectional"))
    )
    (net (code "42") (name "Net-(U1-XIN)") (class "Default")
      (node (ref "C12") (pin "1") (pinfunction "1_1") (pintype "input"))
      (node (ref "U1") (pin "20") (pinfunction "XIN_20") (pintype "input"))
      (node (ref "U4") (pin "1") (pinfunction "1_1") (pintype "input"))
    )
    (net (code "43") (name "Net-(U1-XOUT)") (class "Default")
      (node (ref "R32") (pin "2") (pinfunction "2_2") (pintype "input"))
      (node (ref "U1") (pin "21") (pinfunction "XOUT_21") (pintype "unspecified"))
    )
    (net (code "44") (name "Net-(U6-CC1)") (class "Default")
      (node (ref "R2") (pin "2") (pinfunction "2_2") (pintype "unspecified"))
      (node (ref "U6") (pin "A5") (pinfunction "CC1_A5") (pintype "unspecified"))
    )
    (net (code "45") (name "Net-(U6-CC2)") (class "Default")
      (node (ref "R1") (pin "2") (pinfunction "2_2") (pintype "unspecified"))
      (node (ref "U6") (pin "B5") (pinfunction "CC2_B5") (pintype "unspecified"))
    )
    (net (code "46") (name "Net-(U7-INNA)") (class "Default")
      (node (ref "C3") (pin "1") (pinfunction "1_1") (pintype "input"))
      (node (ref "R6") (pin "2") (pinfunction "2_2") (pintype "input"))
      (node (ref "U7") (pin "7") (pinfunction "INNA_7") (pintype "unspecified"))
    )
    (net (code "47") (name "Net-(U7-INPA)") (class "Default")
      (node (ref "C3") (pin "2") (pinfunction "2_2") (pintype "input"))
      (node (ref "R7") (pin "2") (pinfunction "2_2") (pintype "input"))
      (node (ref "U7") (pin "8") (pinfunction "INPA_8") (pintype "unspecified"))
    )
    (net (code "48") (name "Net-(U7-RATE)") (class "Default")
      (node (ref "R10") (pin "1") (pinfunction "1_1") (pintype "input"))
      (node (ref "R11") (pin "2") (pinfunction "2_2") (pintype "input"))
      (node (ref "U7") (pin "15") (pinfunction "RATE_15") (pintype "unspecified"))
    )
    (net (code "49") (name "Net-(U7-VBG)") (class "Default")
      (node (ref "C4") (pin "2") (pinfunction "2_2") (pintype "input"))
      (node (ref "U7") (pin "6") (pinfunction "VBG_6") (pintype "unspecified"))
    )
    (net (code "50") (name "Net-(U7-VFB)") (class "Default")
      (node (ref "R8") (pin "1") (pinfunction "1_1") (pintype "input"))
      (node (ref "R9") (pin "2") (pinfunction "2_2") (pintype "input"))
      (node (ref "U7") (pin "4") (pinfunction "VFB_4") (pintype "unspecified"))
    )
    (net (code "51") (name "Net-(U8-FB)") (class "Default")
      (node (ref "R14") (pin "2") (pinfunction "2_2") (pintype "input"))
      (node (ref "R15") (pin "1") (pinfunction "1_1") (pintype "input"))
      (node (ref "U8") (pin "10") (pinfunction "FB_10") (pintype "unspecified"))
    )
    (net (code "52") (name "Net-(U8-LX1)") (class "Default")
      (node (ref "L2") (pin "2") (pinfunction "2_2") (pintype "input"))
      (node (ref "U8") (pin "4") (pinfunction "LX1_4") (pintype "unspecified"))
    )
    (net (code "53") (name "Net-(U8-LX2)") (class "Default")
      (node (ref "L2") (pin "1") (pinfunction "1_1") (pintype "input"))
      (node (ref "U8") (pin "2") (pinfunction "LX2_2") (pintype "unspecified"))
    )
    (net (code "54") (name "Net-(U8-VOUT)") (class "Default")
      (node (ref "R14") (pin "1") (pinfunction "1_1") (pintype "input"))
      (node (ref "U12") (pin "1") (pinfunction "1_1") (pintype "input"))
      (node (ref "U8") (pin "1") (pinfunction "VOUT_1") (pintype "unspecified"))
    )
    (net (code "55") (name "Net-(U10-FB)") (class "Default")
      (node (ref "R17") (pin "2") (pinfunction "2_2") (pintype "input"))
      (node (ref "R18") (pin "1") (pinfunction "1_1") (pintype "input"))
      (node (ref "U10") (pin "10") (pinfunction "FB_10") (pintype "unspecified"))
    )
    (net (code "56") (name "Net-(U10-LX1)") (class "Default")
      (node (ref "L3") (pin "2") (pinfunction "2_2") (pintype "input"))
      (node (ref "U10") (pin "4") (pinfunction "LX1_4") (pintype "unspecified"))
    )
    (net (code "57") (name "Net-(U10-LX2)") (class "Default")
      (node (ref "L3") (pin "1") (pinfunction "1_1") (pintype "input"))
      (node (ref "U10") (pin "2") (pinfunction "LX2_2") (pintype "unspecified"))
    )
    (net (code "58") (name "Net-(U10-VOUT)") (class "Default")
      (node (ref "R17") (pin "1") (pinfunction "1_1") (pintype "input"))
      (node (ref "U10") (pin "1") (pinfunction "VOUT_1") (pintype "unspecified"))
      (node (ref "U11") (pin "1") (pinfunction "1_1") (pintype "input"))
    )
    (net (code "59") (name "Net-(U13-VBAT)") (class "Default")
      (node (ref "BT1") (pin "2") (pinfunction "2_2") (pintype "input"))
      (node (ref "U13") (pin "6") (pinfunction "VBAT_6") (pintype "unspecified"))
    )
    (net (code "60") (name "OLED_SCL") (class "Default")
      (node (ref "OLED1") (pin "3") (pinfunction "SCL_3") (pintype "unspecified"))
      (node (ref "R29") (pin "1") (pinfunction "1_1") (pintype "input"))
      (node (ref "U1") (pin "32") (pinfunction "GPIO21_32") (pintype "bidirectional"))
    )
    (net (code "61") (name "OLED_SDA") (class "Default")
      (node (ref "OLED1") (pin "4") (pinfunction "SDA_4") (pintype "unspecified"))
      (node (ref "R28") (pin "1") (pinfunction "1_1") (pintype "input"))
      (node (ref "U1") (pin "31") (pinfunction "GPIO20_31") (pintype "bidirectional"))
    )
    (net (code "62") (name "PWR_PS") (class "Default")
      (node (ref "R19") (pin "2") (pinfunction "2_2") (pintype "input"))
      (node (ref "U1") (pin "17") (pinfunction "GPIO14_17") (pintype "bidirectional"))
      (node (ref "U10") (pin "7") (pinfunction "PS_7") (pintype "unspecified"))
      (node (ref "U8") (pin "7") (pinfunction "PS_7") (pintype "unspecified"))
    )
    (net (code "63") (name "PWR_SOURCE") (class "Default")
      (node (ref "R16") (pin "1") (pinfunction "1_1") (pintype "input"))
      (node (ref "U1") (pin "16") (pinfunction "GPIO13_16") (pintype "bidirectional"))
      (node (ref "U9") (pin "8") (pinfunction "ST_8") (pintype "unspecified"))
    )
    (net (code "64") (name "RESET") (class "Default")
      (node (ref "H6") (pin "2") (pinfunction "2_2") (pintype "input"))
      (node (ref "U1") (pin "26") (pinfunction "RUN_26") (pintype "input"))
    )
    (net (code "65") (name "RP_SWCLK") (class "Default")
      (node (ref "H5") (pin "1") (pinfunction "1_1") (pintype "unspecified"))
      (node (ref "U1") (pin "24") (pinfunction "SWCLK_24") (pintype "output"))
    )
    (net (code "66") (name "RP_SWD") (class "Default")
      (node (ref "H5") (pin "3") (pinfunction "3_3") (pintype "unspecified"))
      (node (ref "U1") (pin "25") (pinfunction "SWD_25") (pintype "bidirectional"))
    )
    (net (code "67") (name "RTC_1HZ_INT") (class "Default")
      (node (ref "R25") (pin "1") (pinfunction "1_1") (pintype "input"))
      (node (ref "U1") (pin "34") (pinfunction "GPIO22_34") (pintype "bidirectional"))
      (node (ref "U13") (pin "3") (pinfunction "INT#/SQW_3") (pintype "bidirectional"))
    )
    (net (code "68") (name "RTC_SCL") (class "Default")
      (node (ref "R26") (pin "1") (pinfunction "1_1") (pintype "input"))
      (node (ref "U1") (pin "5") (pinfunction "GPIO3_5") (pintype "bidirectional"))
      (node (ref "U13") (pin "8") (pinfunction "SCL_8") (pintype "unspecified"))
    )
    (net (code "69") (name "RTC_SDA") (class "Default")
      (node (ref "R27") (pin "1") (pinfunction "1_1") (pintype "input"))
      (node (ref "U1") (pin "4") (pinfunction "GPIO2_4") (pintype "bidirectional"))
      (node (ref "U13") (pin "7") (pinfunction "SDA_7") (pintype "bidirectional"))
    )
    (net (code "70") (name "UART_RX") (class "Default")
      (node (ref "H4") (pin "1") (pinfunction "1_1") (pintype "unspecified"))
      (node (ref "U1") (pin "3") (pinfunction "GPIO1_3") (pintype "bidirectional"))
    )
    (net (code "71") (name "UART_TX") (class "Default")
      (node (ref "H4") (pin "3") (pinfunction "3_3") (pintype "unspecified"))
      (node (ref "U1") (pin "2") (pinfunction "GPIO0_2") (pintype "bidirectional"))
    )
    (net (code "72") (name "USB_DM") (class "Default")
      (node (ref "R13") (pin "2") (pinfunction "2_2") (pintype "input"))
      (node (ref "U6") (pin "A7") (pinfunction "D-_A7") (pintype "unspecified"))
      (node (ref "U6") (pin "B7") (pinfunction "D-_B7") (pintype "unspecified"))
    )
    (net (code "73") (name "USB_DP") (class "Default")
      (node (ref "R12") (pin "2") (pinfunction "2_2") (pintype "input"))
      (node (ref "U6") (pin "A6") (pinfunction "D+_A6") (pintype "unspecified"))
      (node (ref "U6") (pin "B6") (pinfunction "D+_B6") (pintype "unspecified"))
    )
    (net (code "74") (name "VBAT") (class "Default")
      (node (ref "H2") (pin "2") (pinfunction "2_2") (pintype "input"))
      (node (ref "R20") (pin "2") (pinfunction "2_2") (pintype "input"))
      (node (ref "U9") (pin "6") (pinfunction "VIN2_6") (pintype "unspecified"))
    )
    (net (code "75") (name "VBAT_MON") (class "Default")
      (node (ref "R20") (pin "1") (pinfunction "1_1") (pintype "input"))
      (node (ref "R21") (pin "2") (pinfunction "2_2") (pintype "input"))
      (node (ref "U1") (pin "38") (pinfunction "GPIO26_ADC0_38") (pintype "bidirectional"))
    )
    (net (code "76") (name "VBUS") (class "Default")
      (node (ref "R16") (pin "2") (pinfunction "2_2") (pintype "input"))
      (node (ref "R22") (pin "2") (pinfunction "2_2") (pintype "input"))
      (node (ref "U6") (pin "A4B9") (pinfunction "VBUS_A4B9") (pintype "unspecified"))
      (node (ref "U6") (pin "B4A9") (pinfunction "VBUS_B4A9") (pintype "unspecified"))
      (node (ref "U9") (pin "3") (pinfunction "VIN1_3") (pintype "unspecified"))
    )
    (net (code "77") (name "VBUS_MON") (class "Default")
      (node (ref "R22") (pin "1") (pinfunction "1_1") (pintype "input"))
      (node (ref "R23") (pin "2") (pinfunction "2_2") (pintype "input"))
      (node (ref "U1") (pin "39") (pinfunction "GPIO27_ADC1_39") (pintype "bidirectional"))
    )
    (net (code "78") (name "VSRC") (class "Default")
      (node (ref "C8") (pin "1") (pinfunction "1_1") (pintype "input"))
      (node (ref "C9") (pin "1") (pinfunction "1_1") (pintype "input"))
      (node (ref "U10") (pin "5") (pinfunction "VIN_5") (pintype "unspecified"))
      (node (ref "U10") (pin "8") (pinfunction "VINA_8") (pintype "unspecified"))
      (node (ref "U8") (pin "5") (pinfunction "VIN_5") (pintype "unspecified"))
      (node (ref "U8") (pin "6") (pinfunction "EN_6") (pintype "unspecified"))
      (node (ref "U8") (pin "8") (pinfunction "VINA_8") (pintype "unspecified"))
      (node (ref "U9") (pin "2") (pinfunction "VOUT_2") (pintype "unspecified"))
      (node (ref "U9") (pin "7") (pinfunction "VOUT_7") (pintype "unspecified"))
    )
    (net (code "79") (name "unconnected-(LED1-DO-Pad2)") (class "Default")
      (node (ref "LED1") (pin "2") (pinfunction "DO_2") (pintype "unspecified+no_connect"))
    )
    (net (code "80") (name "unconnected-(SCREW1-Pad1)") (class "Default")
      (node (ref "SCREW1") (pin "1") (pinfunction "1_1") (pintype "input"))
    )
    (net (code "81") (name "unconnected-(SCREW2-Pad1)") (class "Default")
      (node (ref "SCREW2") (pin "1") (pinfunction "1_1") (pintype "input"))
    )
    (net (code "82") (name "unconnected-(SCREW3-Pad1)") (class "Default")
      (node (ref "SCREW3") (pin "1") (pinfunction "1_1") (pintype "input"))
    )
    (net (code "83") (name "unconnected-(U1-GPIO5-Pad7)") (class "Default")
      (node (ref "U1") (pin "7") (pinfunction "GPIO5_7") (pintype "bidirectional+no_connect"))
    )
    (net (code "84") (name "unconnected-(U1-GPIO6-Pad8)") (class "Default")
      (node (ref "U1") (pin "8") (pinfunction "GPIO6_8") (pintype "bidirectional+no_connect"))
    )
    (net (code "85") (name "unconnected-(U1-GPIO7-Pad9)") (class "Default")
      (node (ref "U1") (pin "9") (pinfunction "GPIO7_9") (pintype "bidirectional+no_connect"))
    )
    (net (code "86") (name "unconnected-(U1-GPIO8-Pad11)") (class "Default")
      (node (ref "U1") (pin "11") (pinfunction "GPIO8_11") (pintype "bidirectional+no_connect"))
    )
    (net (code "87") (name "unconnected-(U1-GPIO9-Pad12)") (class "Default")
      (node (ref "U1") (pin "12") (pinfunction "GPIO9_12") (pintype "bidirectional+no_connect"))
    )
    (net (code "88") (name "unconnected-(U1-GPIO10-Pad13)") (class "Default")
      (node (ref "U1") (pin "13") (pinfunction "GPIO10_13") (pintype "bidirectional+no_connect"))
    )
    (net (code "89") (name "unconnected-(U1-GPIO11-Pad14)") (class "Default")
      (node (ref "U1") (pin "14") (pinfunction "GPIO11_14") (pintype "bidirectional+no_connect"))
    )
    (net (code "90") (name "unconnected-(U1-GPIO12-Pad15)") (class "Default")
      (node (ref "U1") (pin "15") (pinfunction "GPIO12_15") (pintype "bidirectional+no_connect"))
    )
    (net (code "91") (name "unconnected-(U1-GPIO19-Pad30)") (class "Default")
      (node (ref "U1") (pin "30") (pinfunction "GPIO19_30") (pintype "bidirectional+no_connect"))
    )
    (net (code "92") (name "unconnected-(U1-GPIO28_ADC2-Pad40)") (class "Default")
      (node (ref "U1") (pin "40") (pinfunction "GPIO28_ADC2_40") (pintype "bidirectional+no_connect"))
    )
    (net (code "93") (name "unconnected-(U1-GPIO29_ADC3-Pad41)") (class "Default")
      (node (ref "U1") (pin "41") (pinfunction "GPIO29_ADC3_41") (pintype "bidirectional+no_connect"))
    )
    (net (code "94") (name "unconnected-(U6-SBU1-PadA8)") (class "Default")
      (node (ref "U6") (pin "A8") (pinfunction "SBU1_A8") (pintype "unspecified+no_connect"))
    )
    (net (code "95") (name "unconnected-(U6-SBU2-PadB8)") (class "Default")
      (node (ref "U6") (pin "B8") (pinfunction "SBU2_B8") (pintype "unspecified+no_connect"))
    )
    (net (code "96") (name "unconnected-(U7-XO-Pad13)") (class "Default")
      (node (ref "U7") (pin "13") (pinfunction "XO_13") (pintype "unspecified+no_connect"))
    )
    (net (code "97") (name "unconnected-(U13-32kHz-Pad1)") (class "Default")
      (node (ref "U13") (pin "1") (pinfunction "32kHz_1") (pintype "unspecified+no_connect"))
    )
    (net (code "98") (name "unconnected-(U13-RST#-Pad4)") (class "Default")
      (node (ref "U13") (pin "4") (pinfunction "RST#_4") (pintype "bidirectional+no_connect"))
    )
  )
)
